# SoC_pwr_1.net
KiCad netlist of a schematic drawn in Altium Designer
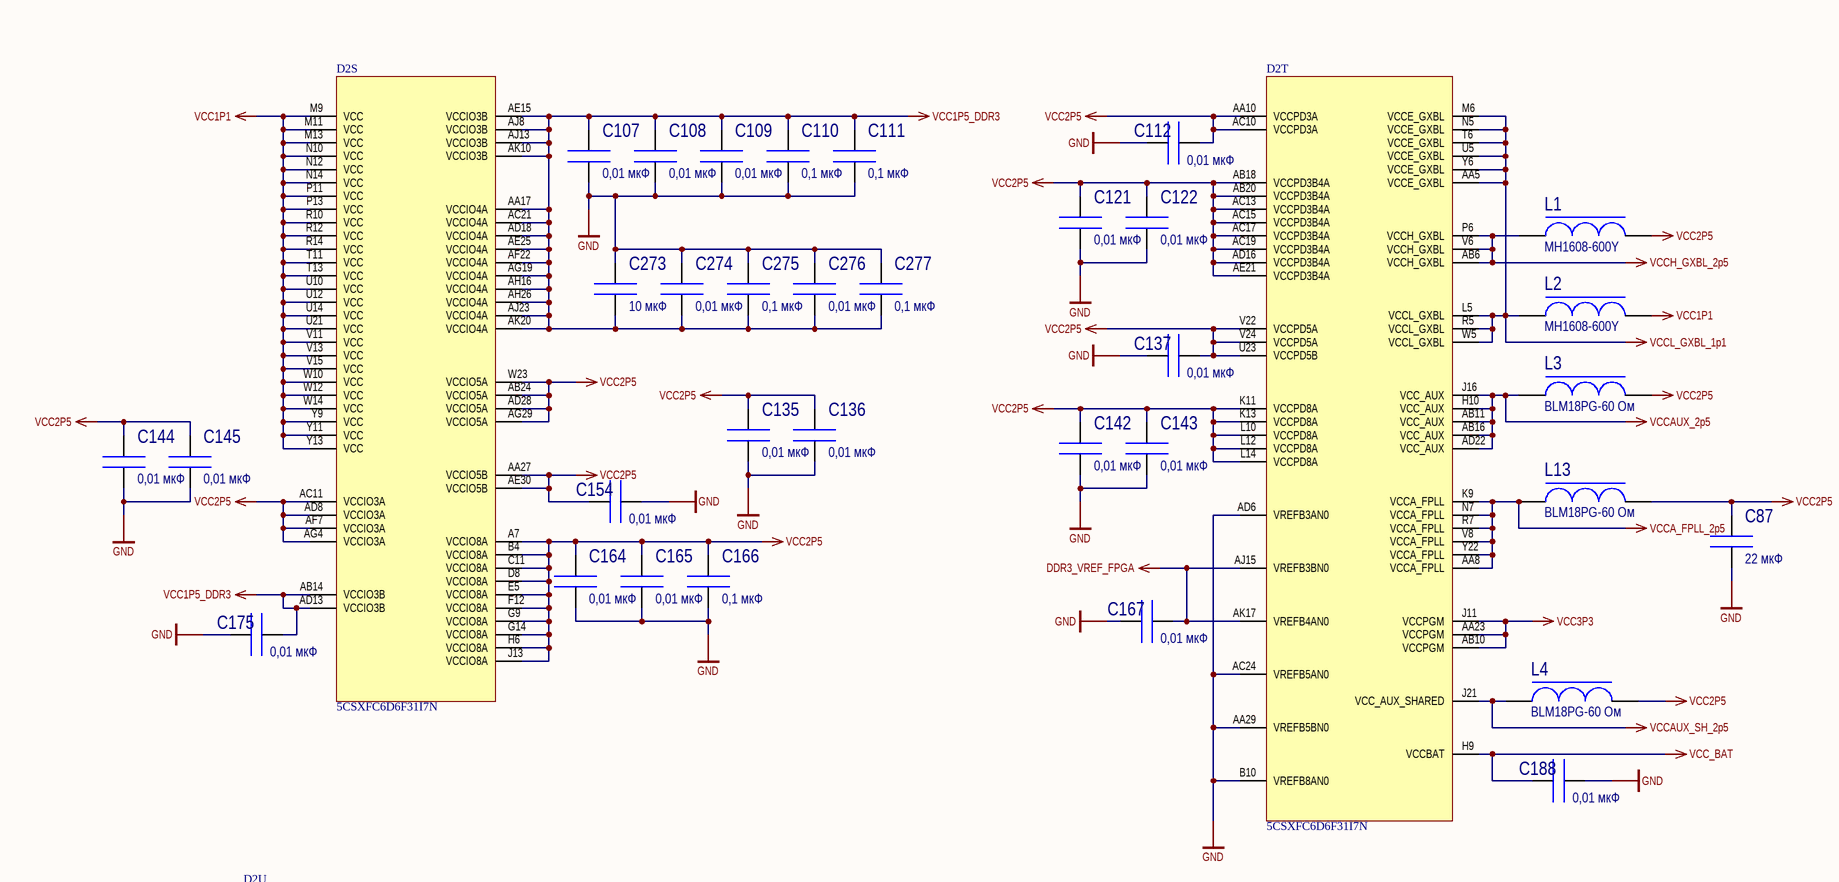
[diagram p0: SoC_pwr_1.SchDoc, top left]
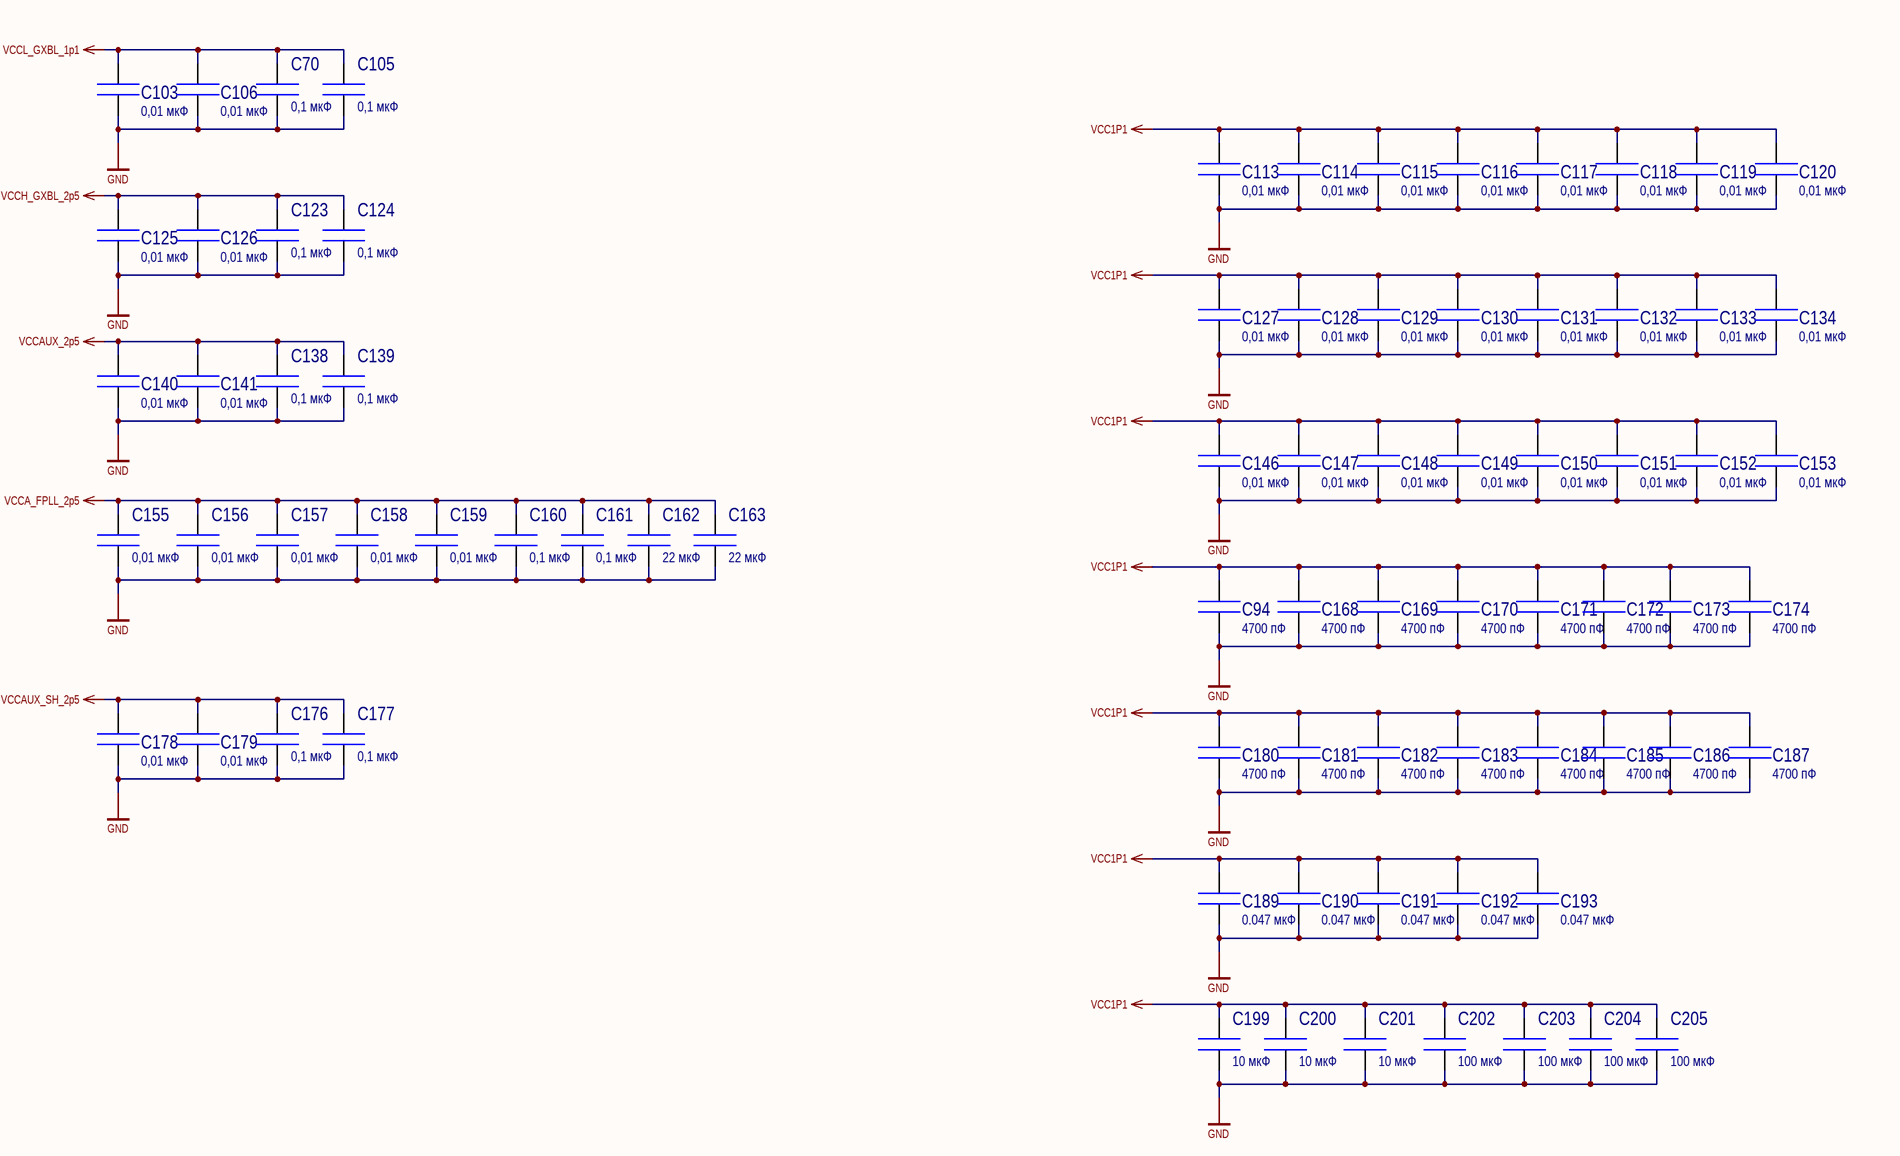
[diagram p1: SoC_pwr_1.SchDoc, top right]
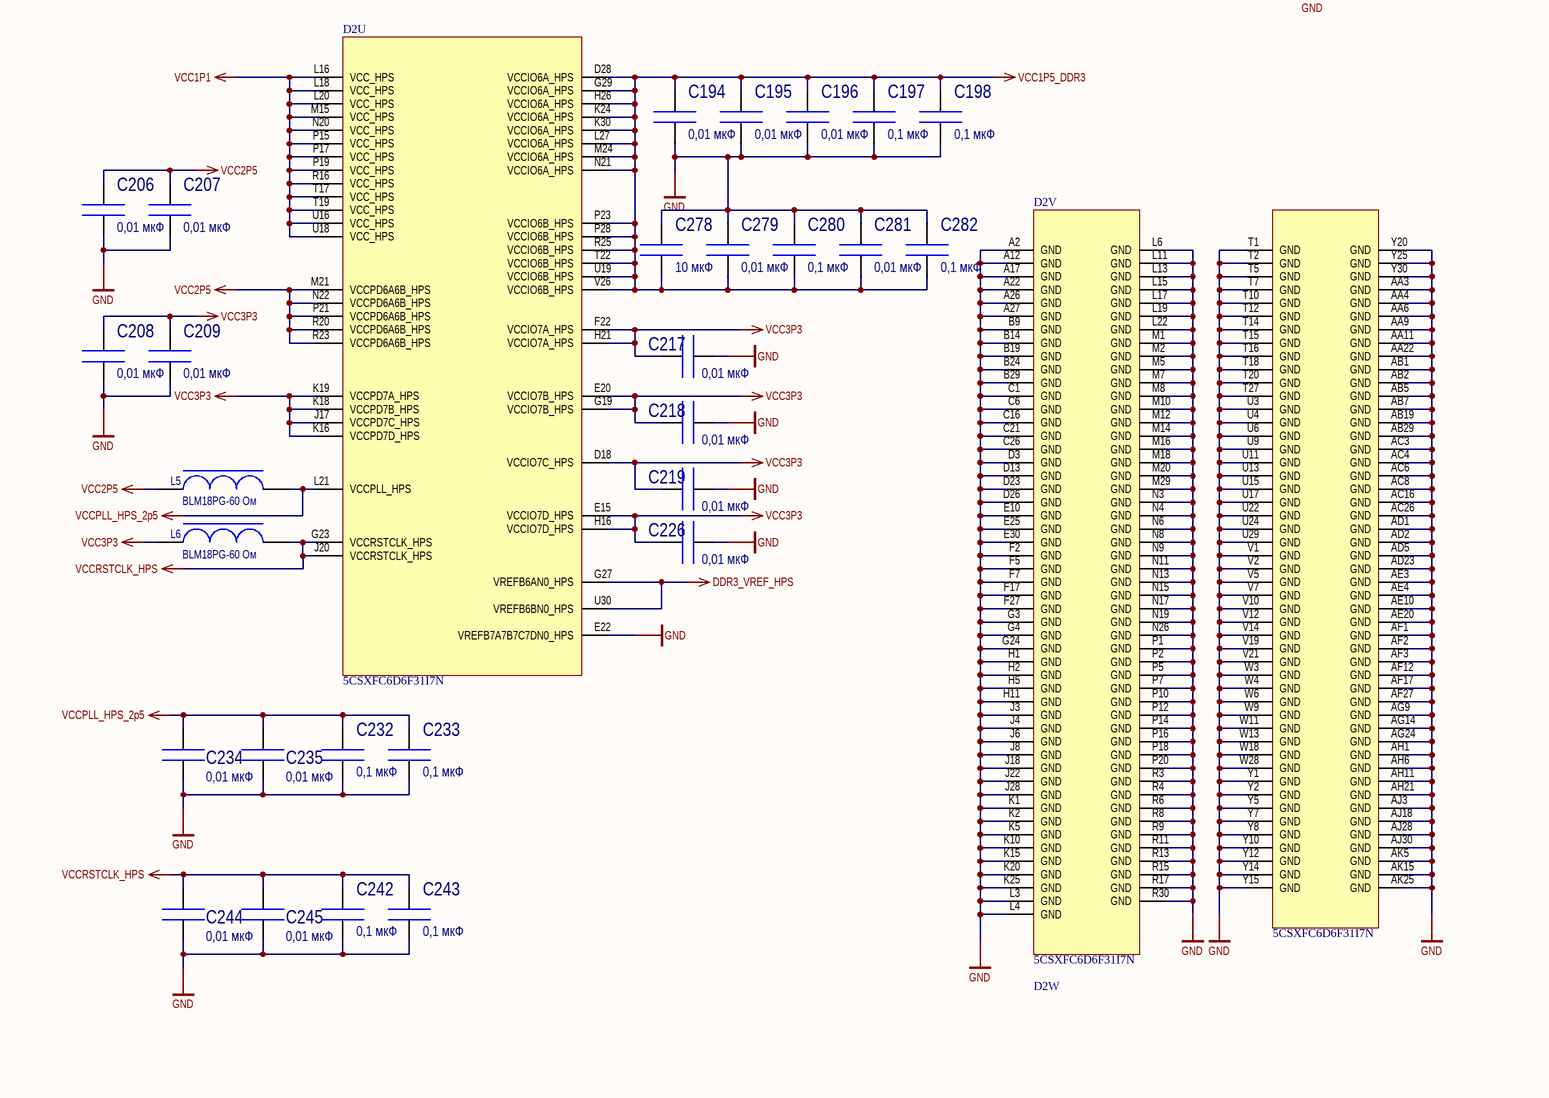
[diagram p2: SoC_pwr_1.SchDoc, bottom left]
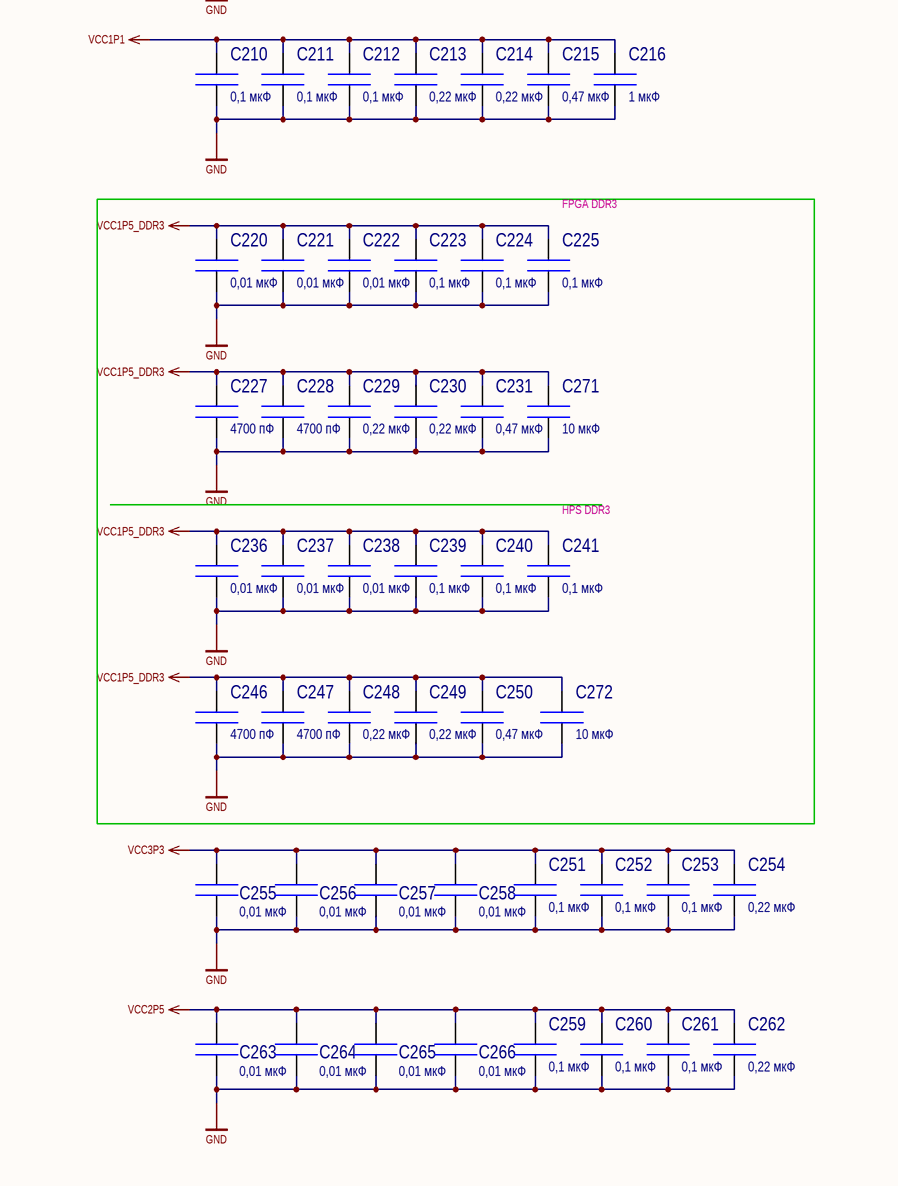
[diagram p3: SoC_pwr_1.SchDoc, bottom right]

(export (version "E")
  (design (tool "Eeschema 10.0.6"))
  (components
    (comp (ref "C70")
      (value "0,1 мкФ")
      (footprint "CC0402(1005)_OCT")
      (description "Чип конденсатор керамический")
      (fields (field (name "Comment") "CC0402-X7R-0,1 мкФ-20%-10В"))
      (libsource (lib "Чип конденсаторы") (part "CC0402-X7R-#-20%-10В"))
    )
    (comp (ref "C87")
      (value "22 мкФ")
      (footprint "CC0603")
      (description "Чип конденсатор керамический")
      (fields (field (name "Comment") "CC0603-X5R-22 мкФ-20%-6,3В"))
      (libsource (lib "Конденсаторы") (part "CC0603-X5R-#-20%-6,3В"))
    )
    (comp (ref "C94")
      (value "4700 пФ")
      (footprint "CC0402(1005)_OCT")
      (description "Чип конденсатор керамический")
      (fields (field (name "Comment") "CC0402-X7R-4700 пФ-10%-50В"))
      (libsource (lib "Чип конденсаторы") (part "CC0402-X7R-#-20%-10В"))
    )
    (comp (ref "C103")
      (value "0,01 мкФ")
      (footprint "CC0402(1005)_OCT")
      (description "Чип конденсатор керамический")
      (fields (field (name "Comment") "CC0402-X7R-0,01 мкФ-10%-50В"))
      (libsource (lib "Чип конденсаторы") (part "CC0402-X7R-#-20%-10В"))
    )
    (comp (ref "C105")
      (value "0,1 мкФ")
      (footprint "CC0402(1005)_OCT")
      (description "Чип конденсатор керамический")
      (fields (field (name "Comment") "CC0402-X7R-0,1 мкФ-20%-10В"))
      (libsource (lib "Чип конденсаторы") (part "CC0402-X7R-#-20%-10В"))
    )
    (comp (ref "C106")
      (value "0,01 мкФ")
      (footprint "CC0402(1005)_OCT")
      (description "Чип конденсатор керамический")
      (fields (field (name "Comment") "CC0402-X7R-0,01 мкФ-10%-50В"))
      (libsource (lib "Чип конденсаторы") (part "CC0402-X7R-#-20%-10В"))
    )
    (comp (ref "C107")
      (value "0,01 мкФ")
      (footprint "CC0402(1005)_OCT")
      (description "Чип конденсатор керамический")
      (fields (field (name "Comment") "CC0402-X7R-0,01 мкФ-10%-50В"))
      (libsource (lib "Чип конденсаторы") (part "CC0402-X7R-#-20%-10В"))
    )
    (comp (ref "C108")
      (value "0,01 мкФ")
      (footprint "CC0402(1005)_OCT")
      (description "Чип конденсатор керамический")
      (fields (field (name "Comment") "CC0402-X7R-0,01 мкФ-10%-50В"))
      (libsource (lib "Чип конденсаторы") (part "CC0402-X7R-#-20%-10В"))
    )
    (comp (ref "C109")
      (value "0,01 мкФ")
      (footprint "CC0402(1005)_OCT")
      (description "Чип конденсатор керамический")
      (fields (field (name "Comment") "CC0402-X7R-0,01 мкФ-10%-50В"))
      (libsource (lib "Чип конденсаторы") (part "CC0402-X7R-#-20%-10В"))
    )
    (comp (ref "C110")
      (value "0,1 мкФ")
      (footprint "CC0402(1005)_OCT")
      (description "Чип конденсатор керамический")
      (fields (field (name "Comment") "CC0402-X7R-0,1 мкФ-20%-10В"))
      (libsource (lib "Чип конденсаторы") (part "CC0402-X7R-#-20%-10В"))
    )
    (comp (ref "C111")
      (value "0,1 мкФ")
      (footprint "CC0402(1005)_OCT")
      (description "Чип конденсатор керамический")
      (fields (field (name "Comment") "CC0402-X7R-0,1 мкФ-20%-10В"))
      (libsource (lib "Чип конденсаторы") (part "CC0402-X7R-#-20%-10В"))
    )
    (comp (ref "C112")
      (value "0,01 мкФ")
      (footprint "CC0402(1005)_OCT")
      (description "Чип конденсатор керамический")
      (fields (field (name "Comment") "CC0402-X7R-0,01 мкФ-10%-50В"))
      (libsource (lib "Чип конденсаторы") (part "CC0402-X7R-#-20%-10В"))
    )
    (comp (ref "C113")
      (value "0,01 мкФ")
      (footprint "CC0402(1005)_OCT")
      (description "Чип конденсатор керамический")
      (fields (field (name "Comment") "CC0402-X7R-0,01 мкФ-10%-50В"))
      (libsource (lib "Чип конденсаторы") (part "CC0402-X7R-#-20%-10В"))
    )
    (comp (ref "C114")
      (value "0,01 мкФ")
      (footprint "CC0402(1005)_OCT")
      (description "Чип конденсатор керамический")
      (fields (field (name "Comment") "CC0402-X7R-0,01 мкФ-10%-50В"))
      (libsource (lib "Чип конденсаторы") (part "CC0402-X7R-#-20%-10В"))
    )
    (comp (ref "C115")
      (value "0,01 мкФ")
      (footprint "CC0402(1005)_OCT")
      (description "Чип конденсатор керамический")
      (fields (field (name "Comment") "CC0402-X7R-0,01 мкФ-10%-50В"))
      (libsource (lib "Чип конденсаторы") (part "CC0402-X7R-#-20%-10В"))
    )
    (comp (ref "C116")
      (value "0,01 мкФ")
      (footprint "CC0402(1005)_OCT")
      (description "Чип конденсатор керамический")
      (fields (field (name "Comment") "CC0402-X7R-0,01 мкФ-10%-50В"))
      (libsource (lib "Чип конденсаторы") (part "CC0402-X7R-#-20%-10В"))
    )
    (comp (ref "C117")
      (value "0,01 мкФ")
      (footprint "CC0402(1005)_OCT")
      (description "Чип конденсатор керамический")
      (fields (field (name "Comment") "CC0402-X7R-0,01 мкФ-10%-50В"))
      (libsource (lib "Чип конденсаторы") (part "CC0402-X7R-#-20%-10В"))
    )
    (comp (ref "C118")
      (value "0,01 мкФ")
      (footprint "CC0402(1005)_OCT")
      (description "Чип конденсатор керамический")
      (fields (field (name "Comment") "CC0402-X7R-0,01 мкФ-10%-50В"))
      (libsource (lib "Чип конденсаторы") (part "CC0402-X7R-#-20%-10В"))
    )
    (comp (ref "C119")
      (value "0,01 мкФ")
      (footprint "CC0402(1005)_OCT")
      (description "Чип конденсатор керамический")
      (fields (field (name "Comment") "CC0402-X7R-0,01 мкФ-10%-50В"))
      (libsource (lib "Чип конденсаторы") (part "CC0402-X7R-#-20%-10В"))
    )
    (comp (ref "C120")
      (value "0,01 мкФ")
      (footprint "CC0402(1005)_OCT")
      (description "Чип конденсатор керамический")
      (fields (field (name "Comment") "CC0402-X7R-0,01 мкФ-10%-50В"))
      (libsource (lib "Чип конденсаторы") (part "CC0402-X7R-#-20%-10В"))
    )
    (comp (ref "C121")
      (value "0,01 мкФ")
      (footprint "CC0402(1005)_OCT")
      (description "Чип конденсатор керамический")
      (fields (field (name "Comment") "CC0402-X7R-0,01 мкФ-10%-50В"))
      (libsource (lib "Чип конденсаторы") (part "CC0402-X7R-#-20%-10В"))
    )
    (comp (ref "C122")
      (value "0,01 мкФ")
      (footprint "CC0402(1005)_OCT")
      (description "Чип конденсатор керамический")
      (fields (field (name "Comment") "CC0402-X7R-0,01 мкФ-10%-50В"))
      (libsource (lib "Чип конденсаторы") (part "CC0402-X7R-#-20%-10В"))
    )
    (comp (ref "C123")
      (value "0,1 мкФ")
      (footprint "CC0402(1005)_OCT")
      (description "Чип конденсатор керамический")
      (fields (field (name "Comment") "CC0402-X7R-0,1 мкФ-20%-10В"))
      (libsource (lib "Чип конденсаторы") (part "CC0402-X7R-#-20%-10В"))
    )
    (comp (ref "C124")
      (value "0,1 мкФ")
      (footprint "CC0402(1005)_OCT")
      (description "Чип конденсатор керамический")
      (fields (field (name "Comment") "CC0402-X7R-0,1 мкФ-20%-10В"))
      (libsource (lib "Чип конденсаторы") (part "CC0402-X7R-#-20%-10В"))
    )
    (comp (ref "C125")
      (value "0,01 мкФ")
      (footprint "CC0402(1005)_OCT")
      (description "Чип конденсатор керамический")
      (fields (field (name "Comment") "CC0402-X7R-0,01 мкФ-10%-50В"))
      (libsource (lib "Чип конденсаторы") (part "CC0402-X7R-#-20%-10В"))
    )
    (comp (ref "C126")
      (value "0,01 мкФ")
      (footprint "CC0402(1005)_OCT")
      (description "Чип конденсатор керамический")
      (fields (field (name "Comment") "CC0402-X7R-0,01 мкФ-10%-50В"))
      (libsource (lib "Чип конденсаторы") (part "CC0402-X7R-#-20%-10В"))
    )
    (comp (ref "C127")
      (value "0,01 мкФ")
      (footprint "CC0402(1005)_OCT")
      (description "Чип конденсатор керамический")
      (fields (field (name "Comment") "CC0402-X7R-0,01 мкФ-10%-50В"))
      (libsource (lib "Чип конденсаторы") (part "CC0402-X7R-#-20%-10В"))
    )
    (comp (ref "C128")
      (value "0,01 мкФ")
      (footprint "CC0402(1005)_OCT")
      (description "Чип конденсатор керамический")
      (fields (field (name "Comment") "CC0402-X7R-0,01 мкФ-10%-50В"))
      (libsource (lib "Чип конденсаторы") (part "CC0402-X7R-#-20%-10В"))
    )
    (comp (ref "C129")
      (value "0,01 мкФ")
      (footprint "CC0402(1005)_OCT")
      (description "Чип конденсатор керамический")
      (fields (field (name "Comment") "CC0402-X7R-0,01 мкФ-10%-50В"))
      (libsource (lib "Чип конденсаторы") (part "CC0402-X7R-#-20%-10В"))
    )
    (comp (ref "C130")
      (value "0,01 мкФ")
      (footprint "CC0402(1005)_OCT")
      (description "Чип конденсатор керамический")
      (fields (field (name "Comment") "CC0402-X7R-0,01 мкФ-10%-50В"))
      (libsource (lib "Чип конденсаторы") (part "CC0402-X7R-#-20%-10В"))
    )
    (comp (ref "C131")
      (value "0,01 мкФ")
      (footprint "CC0402(1005)_OCT")
      (description "Чип конденсатор керамический")
      (fields (field (name "Comment") "CC0402-X7R-0,01 мкФ-10%-50В"))
      (libsource (lib "Чип конденсаторы") (part "CC0402-X7R-#-20%-10В"))
    )
    (comp (ref "C132")
      (value "0,01 мкФ")
      (footprint "CC0402(1005)_OCT")
      (description "Чип конденсатор керамический")
      (fields (field (name "Comment") "CC0402-X7R-0,01 мкФ-10%-50В"))
      (libsource (lib "Чип конденсаторы") (part "CC0402-X7R-#-20%-10В"))
    )
    (comp (ref "C133")
      (value "0,01 мкФ")
      (footprint "CC0402(1005)_OCT")
      (description "Чип конденсатор керамический")
      (fields (field (name "Comment") "CC0402-X7R-0,01 мкФ-10%-50В"))
      (libsource (lib "Чип конденсаторы") (part "CC0402-X7R-#-20%-10В"))
    )
    (comp (ref "C134")
      (value "0,01 мкФ")
      (footprint "CC0402(1005)_OCT")
      (description "Чип конденсатор керамический")
      (fields (field (name "Comment") "CC0402-X7R-0,01 мкФ-10%-50В"))
      (libsource (lib "Чип конденсаторы") (part "CC0402-X7R-#-20%-10В"))
    )
    (comp (ref "C135")
      (value "0,01 мкФ")
      (footprint "CC0402(1005)_OCT")
      (description "Чип конденсатор керамический")
      (fields (field (name "Comment") "CC0402-X7R-0,01 мкФ-10%-50В"))
      (libsource (lib "Чип конденсаторы") (part "CC0402-X7R-#-20%-10В"))
    )
    (comp (ref "C136")
      (value "0,01 мкФ")
      (footprint "CC0402(1005)_OCT")
      (description "Чип конденсатор керамический")
      (fields (field (name "Comment") "CC0402-X7R-0,01 мкФ-10%-50В"))
      (libsource (lib "Чип конденсаторы") (part "CC0402-X7R-#-20%-10В"))
    )
    (comp (ref "C137")
      (value "0,01 мкФ")
      (footprint "CC0402(1005)_OCT")
      (description "Чип конденсатор керамический")
      (fields (field (name "Comment") "CC0402-X7R-0,01 мкФ-10%-50В"))
      (libsource (lib "Чип конденсаторы") (part "CC0402-X7R-#-20%-10В"))
    )
    (comp (ref "C138")
      (value "0,1 мкФ")
      (footprint "CC0402(1005)_OCT")
      (description "Чип конденсатор керамический")
      (fields (field (name "Comment") "CC0402-X7R-0,1 мкФ-20%-10В"))
      (libsource (lib "Чип конденсаторы") (part "CC0402-X7R-#-20%-10В"))
    )
    (comp (ref "C139")
      (value "0,1 мкФ")
      (footprint "CC0402(1005)_OCT")
      (description "Чип конденсатор керамический")
      (fields (field (name "Comment") "CC0402-X7R-0,1 мкФ-20%-10В"))
      (libsource (lib "Чип конденсаторы") (part "CC0402-X7R-#-20%-10В"))
    )
    (comp (ref "C140")
      (value "0,01 мкФ")
      (footprint "CC0402(1005)_OCT")
      (description "Чип конденсатор керамический")
      (fields (field (name "Comment") "CC0402-X7R-0,01 мкФ-10%-50В"))
      (libsource (lib "Чип конденсаторы") (part "CC0402-X7R-#-20%-10В"))
    )
    (comp (ref "C141")
      (value "0,01 мкФ")
      (footprint "CC0402(1005)_OCT")
      (description "Чип конденсатор керамический")
      (fields (field (name "Comment") "CC0402-X7R-0,01 мкФ-10%-50В"))
      (libsource (lib "Чип конденсаторы") (part "CC0402-X7R-#-20%-10В"))
    )
    (comp (ref "C142")
      (value "0,01 мкФ")
      (footprint "CC0402(1005)_OCT")
      (description "Чип конденсатор керамический")
      (fields (field (name "Comment") "CC0402-X7R-0,01 мкФ-10%-50В"))
      (libsource (lib "Чип конденсаторы") (part "CC0402-X7R-#-20%-10В"))
    )
    (comp (ref "C143")
      (value "0,01 мкФ")
      (footprint "CC0402(1005)_OCT")
      (description "Чип конденсатор керамический")
      (fields (field (name "Comment") "CC0402-X7R-0,01 мкФ-10%-50В"))
      (libsource (lib "Чип конденсаторы") (part "CC0402-X7R-#-20%-10В"))
    )
    (comp (ref "C144")
      (value "0,01 мкФ")
      (footprint "CC0402(1005)_OCT")
      (description "Чип конденсатор керамический")
      (fields (field (name "Comment") "CC0402-X7R-0,01 мкФ-10%-50В"))
      (libsource (lib "Чип конденсаторы") (part "CC0402-X7R-#-20%-10В"))
    )
    (comp (ref "C145")
      (value "0,01 мкФ")
      (footprint "CC0402(1005)_OCT")
      (description "Чип конденсатор керамический")
      (fields (field (name "Comment") "CC0402-X7R-0,01 мкФ-10%-50В"))
      (libsource (lib "Чип конденсаторы") (part "CC0402-X7R-#-20%-10В"))
    )
    (comp (ref "C146")
      (value "0,01 мкФ")
      (footprint "CC0402(1005)_OCT")
      (description "Чип конденсатор керамический")
      (fields (field (name "Comment") "CC0402-X7R-0,01 мкФ-10%-50В"))
      (libsource (lib "Чип конденсаторы") (part "CC0402-X7R-#-20%-10В"))
    )
    (comp (ref "C147")
      (value "0,01 мкФ")
      (footprint "CC0402(1005)_OCT")
      (description "Чип конденсатор керамический")
      (fields (field (name "Comment") "CC0402-X7R-0,01 мкФ-10%-50В"))
      (libsource (lib "Чип конденсаторы") (part "CC0402-X7R-#-20%-10В"))
    )
    (comp (ref "C148")
      (value "0,01 мкФ")
      (footprint "CC0402(1005)_OCT")
      (description "Чип конденсатор керамический")
      (fields (field (name "Comment") "CC0402-X7R-0,01 мкФ-10%-50В"))
      (libsource (lib "Чип конденсаторы") (part "CC0402-X7R-#-20%-10В"))
    )
    (comp (ref "C149")
      (value "0,01 мкФ")
      (footprint "CC0402(1005)_OCT")
      (description "Чип конденсатор керамический")
      (fields (field (name "Comment") "CC0402-X7R-0,01 мкФ-10%-50В"))
      (libsource (lib "Чип конденсаторы") (part "CC0402-X7R-#-20%-10В"))
    )
    (comp (ref "C150")
      (value "0,01 мкФ")
      (footprint "CC0402(1005)_OCT")
      (description "Чип конденсатор керамический")
      (fields (field (name "Comment") "CC0402-X7R-0,01 мкФ-10%-50В"))
      (libsource (lib "Чип конденсаторы") (part "CC0402-X7R-#-20%-10В"))
    )
    (comp (ref "C151")
      (value "0,01 мкФ")
      (footprint "CC0402(1005)_OCT")
      (description "Чип конденсатор керамический")
      (fields (field (name "Comment") "CC0402-X7R-0,01 мкФ-10%-50В"))
      (libsource (lib "Чип конденсаторы") (part "CC0402-X7R-#-20%-10В"))
    )
    (comp (ref "C152")
      (value "0,01 мкФ")
      (footprint "CC0402(1005)_OCT")
      (description "Чип конденсатор керамический")
      (fields (field (name "Comment") "CC0402-X7R-0,01 мкФ-10%-50В"))
      (libsource (lib "Чип конденсаторы") (part "CC0402-X7R-#-20%-10В"))
    )
    (comp (ref "C153")
      (value "0,01 мкФ")
      (footprint "CC0402(1005)_OCT")
      (description "Чип конденсатор керамический")
      (fields (field (name "Comment") "CC0402-X7R-0,01 мкФ-10%-50В"))
      (libsource (lib "Чип конденсаторы") (part "CC0402-X7R-#-20%-10В"))
    )
    (comp (ref "C154")
      (value "0,01 мкФ")
      (footprint "CC0402(1005)_OCT")
      (description "Чип конденсатор керамический")
      (fields (field (name "Comment") "CC0402-X7R-0,01 мкФ-10%-50В"))
      (libsource (lib "Чип конденсаторы") (part "CC0402-X7R-#-20%-10В"))
    )
    (comp (ref "C155")
      (value "0,01 мкФ")
      (footprint "CC0402(1005)_OCT")
      (description "Чип конденсатор керамический")
      (fields (field (name "Comment") "CC0402-X7R-0,01 мкФ-10%-50В"))
      (libsource (lib "Чип конденсаторы") (part "CC0402-X7R-#-20%-10В"))
    )
    (comp (ref "C156")
      (value "0,01 мкФ")
      (footprint "CC0402(1005)_OCT")
      (description "Чип конденсатор керамический")
      (fields (field (name "Comment") "CC0402-X7R-0,01 мкФ-10%-50В"))
      (libsource (lib "Чип конденсаторы") (part "CC0402-X7R-#-20%-10В"))
    )
    (comp (ref "C157")
      (value "0,01 мкФ")
      (footprint "CC0402(1005)_OCT")
      (description "Чип конденсатор керамический")
      (fields (field (name "Comment") "CC0402-X7R-0,01 мкФ-10%-50В"))
      (libsource (lib "Чип конденсаторы") (part "CC0402-X7R-#-20%-10В"))
    )
    (comp (ref "C158")
      (value "0,01 мкФ")
      (footprint "CC0402(1005)_OCT")
      (description "Чип конденсатор керамический")
      (fields (field (name "Comment") "CC0402-X7R-0,01 мкФ-10%-50В"))
      (libsource (lib "Чип конденсаторы") (part "CC0402-X7R-#-20%-10В"))
    )
    (comp (ref "C159")
      (value "0,01 мкФ")
      (footprint "CC0402(1005)_OCT")
      (description "Чип конденсатор керамический")
      (fields (field (name "Comment") "CC0402-X7R-0,01 мкФ-10%-50В"))
      (libsource (lib "Чип конденсаторы") (part "CC0402-X7R-#-20%-10В"))
    )
    (comp (ref "C160")
      (value "0,1 мкФ")
      (footprint "CC0402(1005)_OCT")
      (description "Чип конденсатор керамический")
      (fields (field (name "Comment") "CC0402-X7R-0,1 мкФ-20%-10В"))
      (libsource (lib "Чип конденсаторы") (part "CC0402-X7R-#-20%-10В"))
    )
    (comp (ref "C161")
      (value "0,1 мкФ")
      (footprint "CC0402(1005)_OCT")
      (description "Чип конденсатор керамический")
      (fields (field (name "Comment") "CC0402-X7R-0,1 мкФ-20%-10В"))
      (libsource (lib "Чип конденсаторы") (part "CC0402-X7R-#-20%-10В"))
    )
    (comp (ref "C162")
      (value "22 мкФ")
      (footprint "CC0603")
      (description "Чип конденсатор керамический")
      (fields (field (name "Comment") "CC0603-X5R-22 мкФ-20%-6,3В"))
      (libsource (lib "Конденсаторы") (part "CC0603-X5R-#-20%-6,3В"))
    )
    (comp (ref "C163")
      (value "22 мкФ")
      (footprint "CC0603")
      (description "Чип конденсатор керамический")
      (fields (field (name "Comment") "CC0603-X5R-22 мкФ-20%-6,3В"))
      (libsource (lib "Конденсаторы") (part "CC0603-X5R-#-20%-6,3В"))
    )
    (comp (ref "C164")
      (value "0,01 мкФ")
      (footprint "CC0402(1005)_OCT")
      (description "Чип конденсатор керамический")
      (fields (field (name "Comment") "CC0402-X7R-0,01 мкФ-10%-50В"))
      (libsource (lib "Чип конденсаторы") (part "CC0402-X7R-#-20%-10В"))
    )
    (comp (ref "C165")
      (value "0,01 мкФ")
      (footprint "CC0402(1005)_OCT")
      (description "Чип конденсатор керамический")
      (fields (field (name "Comment") "CC0402-X7R-0,01 мкФ-10%-50В"))
      (libsource (lib "Чип конденсаторы") (part "CC0402-X7R-#-20%-10В"))
    )
    (comp (ref "C166")
      (value "0,1 мкФ")
      (footprint "CC0402(1005)_OCT")
      (description "Чип конденсатор керамический")
      (fields (field (name "Comment") "CC0402-X7R-0,1 мкФ-20%-10В"))
      (libsource (lib "Чип конденсаторы") (part "CC0402-X7R-#-20%-10В"))
    )
    (comp (ref "C167")
      (value "0,01 мкФ")
      (footprint "CC0402(1005)_OCT")
      (description "Чип конденсатор керамический")
      (fields (field (name "Comment") "CC0402-X7R-0,01 мкФ-10%-50В"))
      (libsource (lib "Чип конденсаторы") (part "CC0402-X7R-#-20%-10В"))
    )
    (comp (ref "C168")
      (value "4700 пФ")
      (footprint "CC0402(1005)_OCT")
      (description "Чип конденсатор керамический")
      (fields (field (name "Comment") "CC0402-X7R-4700 пФ-10%-50В"))
      (libsource (lib "Чип конденсаторы") (part "CC0402-X7R-#-20%-10В"))
    )
    (comp (ref "C169")
      (value "4700 пФ")
      (footprint "CC0402(1005)_OCT")
      (description "Чип конденсатор керамический")
      (fields (field (name "Comment") "CC0402-X7R-4700 пФ-10%-50В"))
      (libsource (lib "Чип конденсаторы") (part "CC0402-X7R-#-20%-10В"))
    )
    (comp (ref "C170")
      (value "4700 пФ")
      (footprint "CC0402(1005)_OCT")
      (description "Чип конденсатор керамический")
      (fields (field (name "Comment") "CC0402-X7R-4700 пФ-10%-50В"))
      (libsource (lib "Чип конденсаторы") (part "CC0402-X7R-#-20%-10В"))
    )
    (comp (ref "C171")
      (value "4700 пФ")
      (footprint "CC0402(1005)_OCT")
      (description "Чип конденсатор керамический")
      (fields (field (name "Comment") "CC0402-X7R-4700 пФ-10%-50В"))
      (libsource (lib "Чип конденсаторы") (part "CC0402-X7R-#-20%-10В"))
    )
    (comp (ref "C172")
      (value "4700 пФ")
      (footprint "CC0402(1005)_OCT")
      (description "Чип конденсатор керамический")
      (fields (field (name "Comment") "CC0402-X7R-4700 пФ-10%-50В"))
      (libsource (lib "Чип конденсаторы") (part "CC0402-X7R-#-20%-10В"))
    )
    (comp (ref "C173")
      (value "4700 пФ")
      (footprint "CC0402(1005)_OCT")
      (description "Чип конденсатор керамический")
      (fields (field (name "Comment") "CC0402-X7R-4700 пФ-10%-50В"))
      (libsource (lib "Чип конденсаторы") (part "CC0402-X7R-#-20%-10В"))
    )
    (comp (ref "C174")
      (value "4700 пФ")
      (footprint "CC0402(1005)_OCT")
      (description "Чип конденсатор керамический")
      (fields (field (name "Comment") "CC0402-X7R-4700 пФ-10%-50В"))
      (libsource (lib "Чип конденсаторы") (part "CC0402-X7R-#-20%-10В"))
    )
    (comp (ref "C175")
      (value "0,01 мкФ")
      (footprint "CC0402(1005)_OCT")
      (description "Чип конденсатор керамический")
      (fields (field (name "Comment") "CC0402-X7R-0,01 мкФ-10%-50В"))
      (libsource (lib "Чип конденсаторы") (part "CC0402-X7R-#-20%-10В"))
    )
    (comp (ref "C176")
      (value "0,1 мкФ")
      (footprint "CC0402(1005)_OCT")
      (description "Чип конденсатор керамический")
      (fields (field (name "Comment") "CC0402-X7R-0,1 мкФ-20%-10В"))
      (libsource (lib "Чип конденсаторы") (part "CC0402-X7R-#-20%-10В"))
    )
    (comp (ref "C177")
      (value "0,1 мкФ")
      (footprint "CC0402(1005)")
      (description "Чип конденсатор керамический")
      (fields (field (name "Comment") "CC0402-X7R-0,1 мкФ-20%-10В"))
      (libsource (lib "Чип конденсаторы") (part "CC0402-X7R-#-20%-10В"))
    )
    (comp (ref "C178")
      (value "0,01 мкФ")
      (footprint "CC0402(1005)_OCT")
      (description "Чип конденсатор керамический")
      (fields (field (name "Comment") "CC0402-X7R-0,01 мкФ-10%-50В"))
      (libsource (lib "Чип конденсаторы") (part "CC0402-X7R-#-20%-10В"))
    )
    (comp (ref "C179")
      (value "0,01 мкФ")
      (footprint "CC0402(1005)")
      (description "Чип конденсатор керамический")
      (fields (field (name "Comment") "CC0402-X7R-0,01 мкФ-10%-50В"))
      (libsource (lib "Чип конденсаторы") (part "CC0402-X7R-#-20%-10В"))
    )
    (comp (ref "C180")
      (value "4700 пФ")
      (footprint "CC0402(1005)_OCT")
      (description "Чип конденсатор керамический")
      (fields (field (name "Comment") "CC0402-X7R-4700 пФ-10%-50В"))
      (libsource (lib "Чип конденсаторы") (part "CC0402-X7R-#-20%-10В"))
    )
    (comp (ref "C181")
      (value "4700 пФ")
      (footprint "CC0402(1005)_OCT")
      (description "Чип конденсатор керамический")
      (fields (field (name "Comment") "CC0402-X7R-4700 пФ-10%-50В"))
      (libsource (lib "Чип конденсаторы") (part "CC0402-X7R-#-20%-10В"))
    )
    (comp (ref "C182")
      (value "4700 пФ")
      (footprint "CC0402(1005)_OCT")
      (description "Чип конденсатор керамический")
      (fields (field (name "Comment") "CC0402-X7R-4700 пФ-10%-50В"))
      (libsource (lib "Чип конденсаторы") (part "CC0402-X7R-#-20%-10В"))
    )
    (comp (ref "C183")
      (value "4700 пФ")
      (footprint "CC0402(1005)_OCT")
      (description "Чип конденсатор керамический")
      (fields (field (name "Comment") "CC0402-X7R-4700 пФ-10%-50В"))
      (libsource (lib "Чип конденсаторы") (part "CC0402-X7R-#-20%-10В"))
    )
    (comp (ref "C184")
      (value "4700 пФ")
      (footprint "CC0402(1005)_OCT")
      (description "Чип конденсатор керамический")
      (fields (field (name "Comment") "CC0402-X7R-4700 пФ-10%-50В"))
      (libsource (lib "Чип конденсаторы") (part "CC0402-X7R-#-20%-10В"))
    )
    (comp (ref "C185")
      (value "4700 пФ")
      (footprint "CC0402(1005)_OCT")
      (description "Чип конденсатор керамический")
      (fields (field (name "Comment") "CC0402-X7R-4700 пФ-10%-50В"))
      (libsource (lib "Чип конденсаторы") (part "CC0402-X7R-#-20%-10В"))
    )
    (comp (ref "C186")
      (value "4700 пФ")
      (footprint "CC0402(1005)_OCT")
      (description "Чип конденсатор керамический")
      (fields (field (name "Comment") "CC0402-X7R-4700 пФ-10%-50В"))
      (libsource (lib "Чип конденсаторы") (part "CC0402-X7R-#-20%-10В"))
    )
    (comp (ref "C187")
      (value "4700 пФ")
      (footprint "CC0402(1005)_OCT")
      (description "Чип конденсатор керамический")
      (fields (field (name "Comment") "CC0402-X7R-4700 пФ-10%-50В"))
      (libsource (lib "Чип конденсаторы") (part "CC0402-X7R-#-20%-10В"))
    )
    (comp (ref "C188")
      (value "0,01 мкФ")
      (footprint "CC0402(1005)_OCT")
      (description "Чип конденсатор керамический")
      (fields (field (name "Comment") "CC0402-X7R-0,01 мкФ-10%-50В"))
      (libsource (lib "Чип конденсаторы") (part "CC0402-X7R-#-20%-10В"))
    )
    (comp (ref "C189")
      (value "0.047 мкФ")
      (footprint "CC0402(1005)_OCT")
      (description "Чип конденсатор керамический")
      (fields (field (name "Comment") "CC0402-X7R-0.047 мкФ-10%-50В"))
      (libsource (lib "Чип конденсаторы") (part "CC0402-X7R-#-20%-10В"))
    )
    (comp (ref "C190")
      (value "0.047 мкФ")
      (footprint "CC0402(1005)_OCT")
      (description "Чип конденсатор керамический")
      (fields (field (name "Comment") "CC0402-X7R-0.047 мкФ-10%-50В"))
      (libsource (lib "Чип конденсаторы") (part "CC0402-X7R-#-20%-10В"))
    )
    (comp (ref "C191")
      (value "0.047 мкФ")
      (footprint "CC0402(1005)_OCT")
      (description "Чип конденсатор керамический")
      (fields (field (name "Comment") "CC0402-X7R-0.047 мкФ-10%-50В"))
      (libsource (lib "Чип конденсаторы") (part "CC0402-X7R-#-20%-10В"))
    )
    (comp (ref "C192")
      (value "0.047 мкФ")
      (footprint "CC0402(1005)_OCT")
      (description "Чип конденсатор керамический")
      (fields (field (name "Comment") "CC0402-X7R-0.047 мкФ-10%-50В"))
      (libsource (lib "Чип конденсаторы") (part "CC0402-X7R-#-20%-10В"))
    )
    (comp (ref "C193")
      (value "0.047 мкФ")
      (footprint "CC0402(1005)_OCT")
      (description "Чип конденсатор керамический")
      (fields (field (name "Comment") "CC0402-X7R-0.047 мкФ-10%-50В"))
      (libsource (lib "Чип конденсаторы") (part "CC0402-X7R-#-20%-10В"))
    )
    (comp (ref "C194")
      (value "0,01 мкФ")
      (footprint "CC0402(1005)_OCT")
      (description "Чип конденсатор керамический")
      (fields (field (name "Comment") "CC0402-X7R-0,01 мкФ-10%-50В"))
      (libsource (lib "Чип конденсаторы") (part "CC0402-X7R-#-20%-10В"))
    )
    (comp (ref "C195")
      (value "0,01 мкФ")
      (footprint "CC0402(1005)_OCT")
      (description "Чип конденсатор керамический")
      (fields (field (name "Comment") "CC0402-X7R-0,01 мкФ-10%-50В"))
      (libsource (lib "Чип конденсаторы") (part "CC0402-X7R-#-20%-10В"))
    )
    (comp (ref "C196")
      (value "0,01 мкФ")
      (footprint "CC0402(1005)_OCT")
      (description "Чип конденсатор керамический")
      (fields (field (name "Comment") "CC0402-X7R-0,01 мкФ-10%-50В"))
      (libsource (lib "Чип конденсаторы") (part "CC0402-X7R-#-20%-10В"))
    )
    (comp (ref "C197")
      (value "0,1 мкФ")
      (footprint "CC0402(1005)_OCT")
      (description "Чип конденсатор керамический")
      (fields (field (name "Comment") "CC0402-X7R-0,1 мкФ-20%-10В"))
      (libsource (lib "Чип конденсаторы") (part "CC0402-X7R-#-20%-10В"))
    )
    (comp (ref "C198")
      (value "0,1 мкФ")
      (footprint "CC0402(1005)_OCT")
      (description "Чип конденсатор керамический")
      (fields (field (name "Comment") "CC0402-X7R-0,1 мкФ-20%-10В"))
      (libsource (lib "Чип конденсаторы") (part "CC0402-X7R-#-20%-10В"))
    )
    (comp (ref "C199")
      (value "10 мкФ")
      (footprint "CC0402(1005)_OCT")
      (description "Чип конденсатор керамический")
      (fields (field (name "Comment") "CC0402-X5R-10 мкФ-20%-6.3В"))
      (libsource (lib "Чип конденсаторы") (part "CC0402-X7R-#-20%-10В"))
    )
    (comp (ref "C200")
      (value "10 мкФ")
      (footprint "CC0402(1005)_OCT")
      (description "Чип конденсатор керамический")
      (fields (field (name "Comment") "CC0402-X5R-10 мкФ-20%-6.3В"))
      (libsource (lib "Чип конденсаторы") (part "CC0402-X7R-#-20%-10В"))
    )
    (comp (ref "C201")
      (value "10 мкФ")
      (footprint "CC0402(1005)_OCT")
      (description "Чип конденсатор керамический")
      (fields (field (name "Comment") "CC0402-X5R-10 мкФ-20%-6.3В"))
      (libsource (lib "Чип конденсаторы") (part "CC0402-X7R-#-20%-10В"))
    )
    (comp (ref "C202")
      (value "100 мкФ")
      (footprint "CC0805")
      (description "Чип конденсатор керамический")
      (fields (field (name "Comment") "CC0805-X5R-100 мкФ-20%-4В"))
      (libsource (lib "Конденсаторы") (part "CC0805-X7R-#-20%-25В"))
    )
    (comp (ref "C203")
      (value "100 мкФ")
      (footprint "CC0805")
      (description "Чип конденсатор керамический")
      (fields (field (name "Comment") "CC0805-X5R-100 мкФ-20%-4В"))
      (libsource (lib "Конденсаторы") (part "CC0805-X7R-#-20%-25В"))
    )
    (comp (ref "C204")
      (value "100 мкФ")
      (footprint "CC0805")
      (description "Чип конденсатор керамический")
      (fields (field (name "Comment") "CC0805-X5R-100 мкФ-20%-4В"))
      (libsource (lib "Конденсаторы") (part "CC0805-X7R-#-20%-25В"))
    )
    (comp (ref "C205")
      (value "100 мкФ")
      (footprint "CC0805")
      (description "Чип конденсатор керамический")
      (fields (field (name "Comment") "CC0805-X5R-100 мкФ-20%-4В"))
      (libsource (lib "Конденсаторы") (part "CC0805-X7R-#-20%-25В"))
    )
    (comp (ref "C206")
      (value "0,01 мкФ")
      (footprint "CC0402(1005)_OCT")
      (description "Чип конденсатор керамический")
      (fields (field (name "Comment") "CC0402-X7R-0,01 мкФ-10%-50В"))
      (libsource (lib "Чип конденсаторы") (part "CC0402-X7R-#-20%-10В"))
    )
    (comp (ref "C207")
      (value "0,01 мкФ")
      (footprint "CC0402(1005)_OCT")
      (description "Чип конденсатор керамический")
      (fields (field (name "Comment") "CC0402-X7R-0,01 мкФ-10%-50В"))
      (libsource (lib "Чип конденсаторы") (part "CC0402-X7R-#-20%-10В"))
    )
    (comp (ref "C208")
      (value "0,01 мкФ")
      (footprint "CC0402(1005)_OCT")
      (description "Чип конденсатор керамический")
      (fields (field (name "Comment") "CC0402-X7R-0,01 мкФ-10%-50В"))
      (libsource (lib "Чип конденсаторы") (part "CC0402-X7R-#-20%-10В"))
    )
    (comp (ref "C209")
      (value "0,01 мкФ")
      (footprint "CC0402(1005)_OCT")
      (description "Чип конденсатор керамический")
      (fields (field (name "Comment") "CC0402-X7R-0,01 мкФ-10%-50В"))
      (libsource (lib "Чип конденсаторы") (part "CC0402-X7R-#-20%-10В"))
    )
    (comp (ref "C210")
      (value "0,1 мкФ")
      (footprint "CC0402(1005)_OCT")
      (description "Чип конденсатор керамический")
      (fields (field (name "Comment") "CC0402-X7R-0,1 мкФ-20%-10В"))
      (libsource (lib "Чип конденсаторы") (part "CC0402-X7R-#-20%-10В"))
    )
    (comp (ref "C211")
      (value "0,1 мкФ")
      (footprint "CC0402(1005)_OCT")
      (description "Чип конденсатор керамический")
      (fields (field (name "Comment") "CC0402-X7R-0,1 мкФ-20%-10В"))
      (libsource (lib "Чип конденсаторы") (part "CC0402-X7R-#-20%-10В"))
    )
    (comp (ref "C212")
      (value "0,1 мкФ")
      (footprint "CC0402(1005)_OCT")
      (description "Чип конденсатор керамический")
      (fields (field (name "Comment") "CC0402-X7R-0,1 мкФ-20%-10В"))
      (libsource (lib "Чип конденсаторы") (part "CC0402-X7R-#-20%-10В"))
    )
    (comp (ref "C213")
      (value "0,22 мкФ")
      (footprint "CC0402(1005)_OCT")
      (description "Чип конденсатор керамический")
      (fields (field (name "Comment") "CC0402-X7R-0,22 мкФ-10%-6.3В"))
      (libsource (lib "Чип конденсаторы") (part "CC0402-X7R-#-20%-10В"))
    )
    (comp (ref "C214")
      (value "0,22 мкФ")
      (footprint "CC0402(1005)_OCT")
      (description "Чип конденсатор керамический")
      (fields (field (name "Comment") "CC0402-X7R-0,22 мкФ-10%-6.3В"))
      (libsource (lib "Чип конденсаторы") (part "CC0402-X7R-#-20%-10В"))
    )
    (comp (ref "C215")
      (value "0,47 мкФ")
      (footprint "CC0402(1005)_OCT")
      (description "Чип конденсатор керамический")
      (fields (field (name "Comment") "CC0402-X7R-0,47 мкФ-10%-6.3В"))
      (libsource (lib "Чип конденсаторы") (part "CC0402-X7R-#-20%-10В"))
    )
    (comp (ref "C216")
      (value "1 мкФ")
      (footprint "CC0402(1005)_OCT")
      (description "Чип конденсатор керамический")
      (fields (field (name "Comment") "CC0402-X5R-1 мкФ-10%-6.3В"))
      (libsource (lib "Чип конденсаторы") (part "CC0402-X7R-#-20%-10В"))
    )
    (comp (ref "C217")
      (value "0,01 мкФ")
      (footprint "CC0402(1005)_OCT")
      (description "Чип конденсатор керамический")
      (fields (field (name "Comment") "CC0402-X7R-0,01 мкФ-10%-50В"))
      (libsource (lib "Чип конденсаторы") (part "CC0402-X7R-#-20%-10В"))
    )
    (comp (ref "C218")
      (value "0,01 мкФ")
      (footprint "CC0402(1005)_OCT")
      (description "Чип конденсатор керамический")
      (fields (field (name "Comment") "CC0402-X7R-0,01 мкФ-10%-50В"))
      (libsource (lib "Чип конденсаторы") (part "CC0402-X7R-#-20%-10В"))
    )
    (comp (ref "C219")
      (value "0,01 мкФ")
      (footprint "CC0402(1005)_OCT")
      (description "Чип конденсатор керамический")
      (fields (field (name "Comment") "CC0402-X7R-0,01 мкФ-10%-50В"))
      (libsource (lib "Чип конденсаторы") (part "CC0402-X7R-#-20%-10В"))
    )
    (comp (ref "C220")
      (value "0,01 мкФ")
      (footprint "CC0402(1005)")
      (description "Чип конденсатор керамический")
      (fields (field (name "Comment") "CC0402-X7R-0,01 мкФ-10%-50В"))
      (libsource (lib "Чип конденсаторы") (part "CC0402-X7R-#-20%-10В"))
    )
    (comp (ref "C221")
      (value "0,01 мкФ")
      (footprint "CC0402(1005)")
      (description "Чип конденсатор керамический")
      (fields (field (name "Comment") "CC0402-X7R-0,01 мкФ-10%-50В"))
      (libsource (lib "Чип конденсаторы") (part "CC0402-X7R-#-20%-10В"))
    )
    (comp (ref "C222")
      (value "0,01 мкФ")
      (footprint "CC0402(1005)")
      (description "Чип конденсатор керамический")
      (fields (field (name "Comment") "CC0402-X7R-0,01 мкФ-10%-50В"))
      (libsource (lib "Чип конденсаторы") (part "CC0402-X7R-#-20%-10В"))
    )
    (comp (ref "C223")
      (value "0,1 мкФ")
      (footprint "CC0402(1005)")
      (description "Чип конденсатор керамический")
      (fields (field (name "Comment") "CC0402-X7R-0,1 мкФ-20%-10В"))
      (libsource (lib "Чип конденсаторы") (part "CC0402-X7R-#-20%-10В"))
    )
    (comp (ref "C224")
      (value "0,1 мкФ")
      (footprint "CC0402(1005)")
      (description "Чип конденсатор керамический")
      (fields (field (name "Comment") "CC0402-X7R-0,1 мкФ-20%-10В"))
      (libsource (lib "Чип конденсаторы") (part "CC0402-X7R-#-20%-10В"))
    )
    (comp (ref "C225")
      (value "0,1 мкФ")
      (footprint "CC0402(1005)")
      (description "Чип конденсатор керамический")
      (fields (field (name "Comment") "CC0402-X7R-0,1 мкФ-20%-10В"))
      (libsource (lib "Чип конденсаторы") (part "CC0402-X7R-#-20%-10В"))
    )
    (comp (ref "C226")
      (value "0,01 мкФ")
      (footprint "CC0402(1005)_OCT")
      (description "Чип конденсатор керамический")
      (fields (field (name "Comment") "CC0402-X7R-0,01 мкФ-10%-50В"))
      (libsource (lib "Чип конденсаторы") (part "CC0402-X7R-#-20%-10В"))
    )
    (comp (ref "C227")
      (value "4700 пФ")
      (footprint "CC0402(1005)")
      (description "Чип конденсатор керамический")
      (fields (field (name "Comment") "CC0402-X7R-4700 пФ-10%-50В"))
      (libsource (lib "Чип конденсаторы") (part "CC0402-X7R-#-20%-10В"))
    )
    (comp (ref "C228")
      (value "4700 пФ")
      (footprint "CC0402(1005)")
      (description "Чип конденсатор керамический")
      (fields (field (name "Comment") "CC0402-X7R-4700 пФ-10%-50В"))
      (libsource (lib "Чип конденсаторы") (part "CC0402-X7R-#-20%-10В"))
    )
    (comp (ref "C229")
      (value "0,22 мкФ")
      (footprint "CC0402(1005)")
      (description "Чип конденсатор керамический")
      (fields (field (name "Comment") "CC0402-X7R-0,22 мкФ-10%-6.3В"))
      (libsource (lib "Чип конденсаторы") (part "CC0402-X7R-#-20%-10В"))
    )
    (comp (ref "C230")
      (value "0,22 мкФ")
      (footprint "CC0402(1005)")
      (description "Чип конденсатор керамический")
      (fields (field (name "Comment") "CC0402-X7R-0,22 мкФ-10%-6.3В"))
      (libsource (lib "Чип конденсаторы") (part "CC0402-X7R-#-20%-10В"))
    )
    (comp (ref "C231")
      (value "0,47 мкФ")
      (footprint "CC0402(1005)")
      (description "Чип конденсатор керамический")
      (fields (field (name "Comment") "CC0402-X7R-0,47 мкФ-10%-6.3В"))
      (libsource (lib "Чип конденсаторы") (part "CC0402-X7R-#-20%-10В"))
    )
    (comp (ref "C232")
      (value "0,1 мкФ")
      (footprint "CC0402(1005)_OCT")
      (description "Чип конденсатор керамический")
      (fields (field (name "Comment") "CC0402-X7R-0,1 мкФ-20%-10В"))
      (libsource (lib "Чип конденсаторы") (part "CC0402-X7R-#-20%-10В"))
    )
    (comp (ref "C233")
      (value "0,1 мкФ")
      (footprint "CC0402(1005)_OCT")
      (description "Чип конденсатор керамический")
      (fields (field (name "Comment") "CC0402-X7R-0,1 мкФ-20%-10В"))
      (libsource (lib "Чип конденсаторы") (part "CC0402-X7R-#-20%-10В"))
    )
    (comp (ref "C234")
      (value "0,01 мкФ")
      (footprint "CC0402(1005)_OCT")
      (description "Чип конденсатор керамический")
      (fields (field (name "Comment") "CC0402-X7R-0,01 мкФ-10%-50В"))
      (libsource (lib "Чип конденсаторы") (part "CC0402-X7R-#-20%-10В"))
    )
    (comp (ref "C235")
      (value "0,01 мкФ")
      (footprint "CC0402(1005)_OCT")
      (description "Чип конденсатор керамический")
      (fields (field (name "Comment") "CC0402-X7R-0,01 мкФ-10%-50В"))
      (libsource (lib "Чип конденсаторы") (part "CC0402-X7R-#-20%-10В"))
    )
    (comp (ref "C236")
      (value "0,01 мкФ")
      (footprint "CC0402(1005)")
      (description "Чип конденсатор керамический")
      (fields (field (name "Comment") "CC0402-X7R-0,01 мкФ-10%-50В"))
      (libsource (lib "Чип конденсаторы") (part "CC0402-X7R-#-20%-10В"))
    )
    (comp (ref "C237")
      (value "0,01 мкФ")
      (footprint "CC0402(1005)")
      (description "Чип конденсатор керамический")
      (fields (field (name "Comment") "CC0402-X7R-0,01 мкФ-10%-50В"))
      (libsource (lib "Чип конденсаторы") (part "CC0402-X7R-#-20%-10В"))
    )
    (comp (ref "C238")
      (value "0,01 мкФ")
      (footprint "CC0402(1005)")
      (description "Чип конденсатор керамический")
      (fields (field (name "Comment") "CC0402-X7R-0,01 мкФ-10%-50В"))
      (libsource (lib "Чип конденсаторы") (part "CC0402-X7R-#-20%-10В"))
    )
    (comp (ref "C239")
      (value "0,1 мкФ")
      (footprint "CC0402(1005)")
      (description "Чип конденсатор керамический")
      (fields (field (name "Comment") "CC0402-X7R-0,1 мкФ-20%-10В"))
      (libsource (lib "Чип конденсаторы") (part "CC0402-X7R-#-20%-10В"))
    )
    (comp (ref "C240")
      (value "0,1 мкФ")
      (footprint "CC0402(1005)")
      (description "Чип конденсатор керамический")
      (fields (field (name "Comment") "CC0402-X7R-0,1 мкФ-20%-10В"))
      (libsource (lib "Чип конденсаторы") (part "CC0402-X7R-#-20%-10В"))
    )
    (comp (ref "C241")
      (value "0,1 мкФ")
      (footprint "CC0402(1005)")
      (description "Чип конденсатор керамический")
      (fields (field (name "Comment") "CC0402-X7R-0,1 мкФ-20%-10В"))
      (libsource (lib "Чип конденсаторы") (part "CC0402-X7R-#-20%-10В"))
    )
    (comp (ref "C242")
      (value "0,1 мкФ")
      (footprint "CC0402(1005)_OCT")
      (description "Чип конденсатор керамический")
      (fields (field (name "Comment") "CC0402-X7R-0,1 мкФ-20%-10В"))
      (libsource (lib "Чип конденсаторы") (part "CC0402-X7R-#-20%-10В"))
    )
    (comp (ref "C243")
      (value "0,1 мкФ")
      (footprint "CC0402(1005)_OCT")
      (description "Чип конденсатор керамический")
      (fields (field (name "Comment") "CC0402-X7R-0,1 мкФ-20%-10В"))
      (libsource (lib "Чип конденсаторы") (part "CC0402-X7R-#-20%-10В"))
    )
    (comp (ref "C244")
      (value "0,01 мкФ")
      (footprint "CC0402(1005)_OCT")
      (description "Чип конденсатор керамический")
      (fields (field (name "Comment") "CC0402-X7R-0,01 мкФ-10%-50В"))
      (libsource (lib "Чип конденсаторы") (part "CC0402-X7R-#-20%-10В"))
    )
    (comp (ref "C245")
      (value "0,01 мкФ")
      (footprint "CC0402(1005)_OCT")
      (description "Чип конденсатор керамический")
      (fields (field (name "Comment") "CC0402-X7R-0,01 мкФ-10%-50В"))
      (libsource (lib "Чип конденсаторы") (part "CC0402-X7R-#-20%-10В"))
    )
    (comp (ref "C246")
      (value "4700 пФ")
      (footprint "CC0402(1005)")
      (description "Чип конденсатор керамический")
      (fields (field (name "Comment") "CC0402-X7R-4700 пФ-10%-50В"))
      (libsource (lib "Чип конденсаторы") (part "CC0402-X7R-#-20%-10В"))
    )
    (comp (ref "C247")
      (value "4700 пФ")
      (footprint "CC0402(1005)")
      (description "Чип конденсатор керамический")
      (fields (field (name "Comment") "CC0402-X7R-4700 пФ-10%-50В"))
      (libsource (lib "Чип конденсаторы") (part "CC0402-X7R-#-20%-10В"))
    )
    (comp (ref "C248")
      (value "0,22 мкФ")
      (footprint "CC0402(1005)")
      (description "Чип конденсатор керамический")
      (fields (field (name "Comment") "CC0402-X7R-0,22 мкФ-10%-6.3В"))
      (libsource (lib "Чип конденсаторы") (part "CC0402-X7R-#-20%-10В"))
    )
    (comp (ref "C249")
      (value "0,22 мкФ")
      (footprint "CC0402(1005)")
      (description "Чип конденсатор керамический")
      (fields (field (name "Comment") "CC0402-X7R-0,22 мкФ-10%-6.3В"))
      (libsource (lib "Чип конденсаторы") (part "CC0402-X7R-#-20%-10В"))
    )
    (comp (ref "C250")
      (value "0,47 мкФ")
      (footprint "CC0402(1005)")
      (description "Чип конденсатор керамический")
      (fields (field (name "Comment") "CC0402-X7R-0,47 мкФ-10%-6.3В"))
      (libsource (lib "Чип конденсаторы") (part "CC0402-X7R-#-20%-10В"))
    )
    (comp (ref "C251")
      (value "0,1 мкФ")
      (footprint "CC0402(1005)_OCT")
      (description "Чип конденсатор керамический")
      (fields (field (name "Comment") "CC0402-X7R-0,1 мкФ-20%-10В"))
      (libsource (lib "Чип конденсаторы") (part "CC0402-X7R-#-20%-10В"))
    )
    (comp (ref "C252")
      (value "0,1 мкФ")
      (footprint "CC0402(1005)_OCT")
      (description "Чип конденсатор керамический")
      (fields (field (name "Comment") "CC0402-X7R-0,1 мкФ-20%-10В"))
      (libsource (lib "Чип конденсаторы") (part "CC0402-X7R-#-20%-10В"))
    )
    (comp (ref "C253")
      (value "0,1 мкФ")
      (footprint "CC0402(1005)_OCT")
      (description "Чип конденсатор керамический")
      (fields (field (name "Comment") "CC0402-X7R-0,1 мкФ-20%-10В"))
      (libsource (lib "Чип конденсаторы") (part "CC0402-X7R-#-20%-10В"))
    )
    (comp (ref "C254")
      (value "0,22 мкФ")
      (footprint "CC0402(1005)_OCT")
      (description "Чип конденсатор керамический")
      (fields (field (name "Comment") "CC0402-X7R-0,22 мкФ-10%-6.3В"))
      (libsource (lib "Чип конденсаторы") (part "CC0402-X7R-#-20%-10В"))
    )
    (comp (ref "C255")
      (value "0,01 мкФ")
      (footprint "CC0402(1005)_OCT")
      (description "Чип конденсатор керамический")
      (fields (field (name "Comment") "CC0402-X7R-0,01 мкФ-10%-50В"))
      (libsource (lib "Чип конденсаторы") (part "CC0402-X7R-#-20%-10В"))
    )
    (comp (ref "C256")
      (value "0,01 мкФ")
      (footprint "CC0402(1005)_OCT")
      (description "Чип конденсатор керамический")
      (fields (field (name "Comment") "CC0402-X7R-0,01 мкФ-10%-50В"))
      (libsource (lib "Чип конденсаторы") (part "CC0402-X7R-#-20%-10В"))
    )
    (comp (ref "C257")
      (value "0,01 мкФ")
      (footprint "CC0402(1005)_OCT")
      (description "Чип конденсатор керамический")
      (fields (field (name "Comment") "CC0402-X7R-0,01 мкФ-10%-50В"))
      (libsource (lib "Чип конденсаторы") (part "CC0402-X7R-#-20%-10В"))
    )
    (comp (ref "C258")
      (value "0,01 мкФ")
      (footprint "CC0402(1005)_OCT")
      (description "Чип конденсатор керамический")
      (fields (field (name "Comment") "CC0402-X7R-0,01 мкФ-10%-50В"))
      (libsource (lib "Чип конденсаторы") (part "CC0402-X7R-#-20%-10В"))
    )
    (comp (ref "C259")
      (value "0,1 мкФ")
      (footprint "CC0402(1005)_OCT")
      (description "Чип конденсатор керамический")
      (fields (field (name "Comment") "CC0402-X7R-0,1 мкФ-20%-10В"))
      (libsource (lib "Чип конденсаторы") (part "CC0402-X7R-#-20%-10В"))
    )
    (comp (ref "C260")
      (value "0,1 мкФ")
      (footprint "CC0402(1005)_OCT")
      (description "Чип конденсатор керамический")
      (fields (field (name "Comment") "CC0402-X7R-0,1 мкФ-20%-10В"))
      (libsource (lib "Чип конденсаторы") (part "CC0402-X7R-#-20%-10В"))
    )
    (comp (ref "C261")
      (value "0,1 мкФ")
      (footprint "CC0402(1005)_OCT")
      (description "Чип конденсатор керамический")
      (fields (field (name "Comment") "CC0402-X7R-0,1 мкФ-20%-10В"))
      (libsource (lib "Чип конденсаторы") (part "CC0402-X7R-#-20%-10В"))
    )
    (comp (ref "C262")
      (value "0,22 мкФ")
      (footprint "CC0402(1005)_OCT")
      (description "Чип конденсатор керамический")
      (fields (field (name "Comment") "CC0402-X7R-0,22 мкФ-10%-6.3В"))
      (libsource (lib "Чип конденсаторы") (part "CC0402-X7R-#-20%-10В"))
    )
    (comp (ref "C263")
      (value "0,01 мкФ")
      (footprint "CC0402(1005)_OCT")
      (description "Чип конденсатор керамический")
      (fields (field (name "Comment") "CC0402-X7R-0,01 мкФ-10%-50В"))
      (libsource (lib "Чип конденсаторы") (part "CC0402-X7R-#-20%-10В"))
    )
    (comp (ref "C264")
      (value "0,01 мкФ")
      (footprint "CC0402(1005)_OCT")
      (description "Чип конденсатор керамический")
      (fields (field (name "Comment") "CC0402-X7R-0,01 мкФ-10%-50В"))
      (libsource (lib "Чип конденсаторы") (part "CC0402-X7R-#-20%-10В"))
    )
    (comp (ref "C265")
      (value "0,01 мкФ")
      (footprint "CC0402(1005)_OCT")
      (description "Чип конденсатор керамический")
      (fields (field (name "Comment") "CC0402-X7R-0,01 мкФ-10%-50В"))
      (libsource (lib "Чип конденсаторы") (part "CC0402-X7R-#-20%-10В"))
    )
    (comp (ref "C266")
      (value "0,01 мкФ")
      (footprint "CC0402(1005)_OCT")
      (description "Чип конденсатор керамический")
      (fields (field (name "Comment") "CC0402-X7R-0,01 мкФ-10%-50В"))
      (libsource (lib "Чип конденсаторы") (part "CC0402-X7R-#-20%-10В"))
    )
    (comp (ref "C271")
      (value "10 мкФ")
      (footprint "CC0402(1005)")
      (description "Чип конденсатор керамический")
      (fields (field (name "Comment") "CC0402-X5R-10 мкФ-20%-6.3В"))
      (libsource (lib "Чип конденсаторы") (part "CC0402-X7R-#-20%-10В"))
    )
    (comp (ref "C272")
      (value "10 мкФ")
      (footprint "CC0402(1005)")
      (description "Чип конденсатор керамический")
      (fields (field (name "Comment") "CC0402-X5R-10 мкФ-20%-6.3В"))
      (libsource (lib "Чип конденсаторы") (part "CC0402-X7R-#-20%-10В"))
    )
    (comp (ref "C273")
      (value "10 мкФ")
      (footprint "CC0402(1005)")
      (description "Чип конденсатор керамический")
      (fields (field (name "Comment") "CC0402-X5R-10 мкФ-20%-6.3В"))
      (libsource (lib "Чип конденсаторы") (part "CC0402-X7R-#-20%-10В"))
    )
    (comp (ref "C274")
      (value "0,01 мкФ")
      (footprint "CC0402(1005)")
      (description "Чип конденсатор керамический")
      (fields (field (name "Comment") "CC0402-X7R-0,01 мкФ-10%-50В"))
      (libsource (lib "Чип конденсаторы") (part "CC0402-X7R-#-20%-10В"))
    )
    (comp (ref "C275")
      (value "0,1 мкФ")
      (footprint "CC0402(1005)")
      (description "Чип конденсатор керамический")
      (fields (field (name "Comment") "CC0402-X7R-0,1 мкФ-20%-10В"))
      (libsource (lib "Чип конденсаторы") (part "CC0402-X7R-#-20%-10В"))
    )
    (comp (ref "C276")
      (value "0,01 мкФ")
      (footprint "CC0402(1005)")
      (description "Чип конденсатор керамический")
      (fields (field (name "Comment") "CC0402-X7R-0,01 мкФ-10%-50В"))
      (libsource (lib "Чип конденсаторы") (part "CC0402-X7R-#-20%-10В"))
    )
    (comp (ref "C277")
      (value "0,1 мкФ")
      (footprint "CC0402(1005)")
      (description "Чип конденсатор керамический")
      (fields (field (name "Comment") "CC0402-X7R-0,1 мкФ-20%-10В"))
      (libsource (lib "Чип конденсаторы") (part "CC0402-X7R-#-20%-10В"))
    )
    (comp (ref "C278")
      (value "10 мкФ")
      (footprint "CC0402(1005)")
      (description "Чип конденсатор керамический")
      (fields (field (name "Comment") "CC0402-X5R-10 мкФ-20%-6.3В"))
      (libsource (lib "Чип конденсаторы") (part "CC0402-X7R-#-20%-10В"))
    )
    (comp (ref "C279")
      (value "0,01 мкФ")
      (footprint "CC0402(1005)")
      (description "Чип конденсатор керамический")
      (fields (field (name "Comment") "CC0402-X7R-0,01 мкФ-10%-50В"))
      (libsource (lib "Чип конденсаторы") (part "CC0402-X7R-#-20%-10В"))
    )
    (comp (ref "C280")
      (value "0,1 мкФ")
      (footprint "CC0402(1005)")
      (description "Чип конденсатор керамический")
      (fields (field (name "Comment") "CC0402-X7R-0,1 мкФ-20%-10В"))
      (libsource (lib "Чип конденсаторы") (part "CC0402-X7R-#-20%-10В"))
    )
    (comp (ref "C281")
      (value "0,01 мкФ")
      (footprint "CC0402(1005)")
      (description "Чип конденсатор керамический")
      (fields (field (name "Comment") "CC0402-X7R-0,01 мкФ-10%-50В"))
      (libsource (lib "Чип конденсаторы") (part "CC0402-X7R-#-20%-10В"))
    )
    (comp (ref "C282")
      (value "0,1 мкФ")
      (footprint "CC0402(1005)")
      (description "Чип конденсатор керамический")
      (fields (field (name "Comment") "CC0402-X7R-0,1 мкФ-20%-10В"))
      (libsource (lib "Чип конденсаторы") (part "CC0402-X7R-#-20%-10В"))
    )
    (comp (ref "D2")
      (value "5CSXFC6D6F31I7N")
      (footprint "ALTR-FBGA896_A-200")
      (fields (field (name "MANUFACTURER") "Altera"))
      (libsource (lib "Altera Cyclone V_sd") (part "5CSXFC6D6F31I7N"))
    )
    (comp (ref "L1")
      (value "MH1608-600Y")
      (footprint "CL0805")
      (description "Чип индуктивность подавления EMP")
      (libsource (lib "Индуктивности") (part "BLM21"))
    )
    (comp (ref "L2")
      (value "MH1608-600Y")
      (footprint "CL0805")
      (description "Чип индуктивность подавления EMP")
      (libsource (lib "Индуктивности") (part "BLM21"))
    )
    (comp (ref "L3")
      (value "BLM18PG-60 Ом")
      (footprint "CL0603")
      (description "Чип индуктивность подавления EMP")
      (libsource (lib "Индуктивности") (part "BLM18"))
    )
    (comp (ref "L4")
      (value "BLM18PG-60 Ом")
      (footprint "CL0603")
      (description "Чип индуктивность подавления EMP")
      (libsource (lib "Индуктивности") (part "BLM18"))
    )
    (comp (ref "L5")
      (value "BLM18PG-60 Ом")
      (footprint "CL0603")
      (description "Чип индуктивность подавления EMP")
      (libsource (lib "Индуктивности") (part "BLM18"))
    )
    (comp (ref "L6")
      (value "BLM18PG-60 Ом")
      (footprint "CL0603")
      (description "Чип индуктивность подавления EMP")
      (libsource (lib "Индуктивности") (part "BLM18"))
    )
    (comp (ref "L13")
      (value "BLM18PG-60 Ом")
      (footprint "CL0603")
      (description "Чип индуктивность подавления EMP")
      (libsource (lib "Индуктивности") (part "BLM18"))
    )
  )
  (nets
    (net (code "1") (name "DDR3_VREF_FPGA") (class "Default")
      (node (ref "C167") (pin "1") (pinfunction "+_1") (pintype "passive"))
      (node (ref "D2") (pin "AJ15") (pinfunction "VREFB3BN0_AJ15") (pintype "power_in"))
      (node (ref "D2") (pin "AK17") (pinfunction "VREFB4AN0_AK17") (pintype "power_in"))
    )
    (net (code "2") (name "DDR3_VREF_HPS") (class "Default")
      (node (ref "D2") (pin "G27") (pinfunction "VREFB6AN0_HPS_G27") (pintype "power_in"))
      (node (ref "D2") (pin "U30") (pinfunction "VREFB6BN0_HPS_U30") (pintype "power_in"))
    )
    (net (code "3") (name "GND") (class "Default")
      (node (ref "C103") (pin "1") (pinfunction "+_1") (pintype "passive"))
      (node (ref "C105") (pin "1") (pinfunction "+_1") (pintype "passive"))
      (node (ref "C106") (pin "1") (pinfunction "+_1") (pintype "passive"))
      (node (ref "C107") (pin "1") (pinfunction "+_1") (pintype "passive"))
      (node (ref "C108") (pin "1") (pinfunction "+_1") (pintype "passive"))
      (node (ref "C109") (pin "1") (pinfunction "+_1") (pintype "passive"))
      (node (ref "C110") (pin "1") (pinfunction "+_1") (pintype "passive"))
      (node (ref "C111") (pin "1") (pinfunction "+_1") (pintype "passive"))
      (node (ref "C112") (pin "2") (pinfunction "-_2") (pintype "passive"))
      (node (ref "C113") (pin "1") (pinfunction "+_1") (pintype "passive"))
      (node (ref "C114") (pin "1") (pinfunction "+_1") (pintype "passive"))
      (node (ref "C115") (pin "1") (pinfunction "+_1") (pintype "passive"))
      (node (ref "C116") (pin "1") (pinfunction "+_1") (pintype "passive"))
      (node (ref "C117") (pin "1") (pinfunction "+_1") (pintype "passive"))
      (node (ref "C118") (pin "1") (pinfunction "+_1") (pintype "passive"))
      (node (ref "C119") (pin "1") (pinfunction "+_1") (pintype "passive"))
      (node (ref "C120") (pin "1") (pinfunction "+_1") (pintype "passive"))
      (node (ref "C121") (pin "1") (pinfunction "+_1") (pintype "passive"))
      (node (ref "C122") (pin "1") (pinfunction "+_1") (pintype "passive"))
      (node (ref "C123") (pin "1") (pinfunction "+_1") (pintype "passive"))
      (node (ref "C124") (pin "1") (pinfunction "+_1") (pintype "passive"))
      (node (ref "C125") (pin "1") (pinfunction "+_1") (pintype "passive"))
      (node (ref "C126") (pin "1") (pinfunction "+_1") (pintype "passive"))
      (node (ref "C127") (pin "1") (pinfunction "+_1") (pintype "passive"))
      (node (ref "C128") (pin "1") (pinfunction "+_1") (pintype "passive"))
      (node (ref "C129") (pin "1") (pinfunction "+_1") (pintype "passive"))
      (node (ref "C130") (pin "1") (pinfunction "+_1") (pintype "passive"))
      (node (ref "C131") (pin "1") (pinfunction "+_1") (pintype "passive"))
      (node (ref "C132") (pin "1") (pinfunction "+_1") (pintype "passive"))
      (node (ref "C133") (pin "1") (pinfunction "+_1") (pintype "passive"))
      (node (ref "C134") (pin "1") (pinfunction "+_1") (pintype "passive"))
      (node (ref "C135") (pin "1") (pinfunction "+_1") (pintype "passive"))
      (node (ref "C136") (pin "1") (pinfunction "+_1") (pintype "passive"))
      (node (ref "C137") (pin "2") (pinfunction "-_2") (pintype "passive"))
      (node (ref "C138") (pin "1") (pinfunction "+_1") (pintype "passive"))
      (node (ref "C139") (pin "1") (pinfunction "+_1") (pintype "passive"))
      (node (ref "C140") (pin "1") (pinfunction "+_1") (pintype "passive"))
      (node (ref "C141") (pin "1") (pinfunction "+_1") (pintype "passive"))
      (node (ref "C142") (pin "1") (pinfunction "+_1") (pintype "passive"))
      (node (ref "C143") (pin "1") (pinfunction "+_1") (pintype "passive"))
      (node (ref "C144") (pin "1") (pinfunction "+_1") (pintype "passive"))
      (node (ref "C145") (pin "1") (pinfunction "+_1") (pintype "passive"))
      (node (ref "C146") (pin "1") (pinfunction "+_1") (pintype "passive"))
      (node (ref "C147") (pin "1") (pinfunction "+_1") (pintype "passive"))
      (node (ref "C148") (pin "1") (pinfunction "+_1") (pintype "passive"))
      (node (ref "C149") (pin "1") (pinfunction "+_1") (pintype "passive"))
      (node (ref "C150") (pin "1") (pinfunction "+_1") (pintype "passive"))
      (node (ref "C151") (pin "1") (pinfunction "+_1") (pintype "passive"))
      (node (ref "C152") (pin "1") (pinfunction "+_1") (pintype "passive"))
      (node (ref "C153") (pin "1") (pinfunction "+_1") (pintype "passive"))
      (node (ref "C154") (pin "2") (pinfunction "-_2") (pintype "passive"))
      (node (ref "C155") (pin "1") (pinfunction "+_1") (pintype "passive"))
      (node (ref "C156") (pin "1") (pinfunction "+_1") (pintype "passive"))
      (node (ref "C157") (pin "1") (pinfunction "+_1") (pintype "passive"))
      (node (ref "C158") (pin "1") (pinfunction "+_1") (pintype "passive"))
      (node (ref "C159") (pin "1") (pinfunction "+_1") (pintype "passive"))
      (node (ref "C160") (pin "1") (pinfunction "+_1") (pintype "passive"))
      (node (ref "C161") (pin "1") (pinfunction "+_1") (pintype "passive"))
      (node (ref "C162") (pin "2") (pinfunction "-_2") (pintype "passive"))
      (node (ref "C163") (pin "2") (pinfunction "-_2") (pintype "passive"))
      (node (ref "C164") (pin "1") (pinfunction "+_1") (pintype "passive"))
      (node (ref "C165") (pin "1") (pinfunction "+_1") (pintype "passive"))
      (node (ref "C166") (pin "1") (pinfunction "+_1") (pintype "passive"))
      (node (ref "C167") (pin "2") (pinfunction "-_2") (pintype "passive"))
      (node (ref "C168") (pin "2") (pinfunction "-_2") (pintype "passive"))
      (node (ref "C169") (pin "2") (pinfunction "-_2") (pintype "passive"))
      (node (ref "C170") (pin "2") (pinfunction "-_2") (pintype "passive"))
      (node (ref "C171") (pin "2") (pinfunction "-_2") (pintype "passive"))
      (node (ref "C172") (pin "2") (pinfunction "-_2") (pintype "passive"))
      (node (ref "C173") (pin "2") (pinfunction "-_2") (pintype "passive"))
      (node (ref "C174") (pin "2") (pinfunction "-_2") (pintype "passive"))
      (node (ref "C175") (pin "2") (pinfunction "-_2") (pintype "passive"))
      (node (ref "C176") (pin "1") (pinfunction "+_1") (pintype "passive"))
      (node (ref "C177") (pin "1") (pinfunction "+_1") (pintype "passive"))
      (node (ref "C178") (pin "1") (pinfunction "+_1") (pintype "passive"))
      (node (ref "C179") (pin "1") (pinfunction "+_1") (pintype "passive"))
      (node (ref "C180") (pin "2") (pinfunction "-_2") (pintype "passive"))
      (node (ref "C181") (pin "2") (pinfunction "-_2") (pintype "passive"))
      (node (ref "C182") (pin "2") (pinfunction "-_2") (pintype "passive"))
      (node (ref "C183") (pin "2") (pinfunction "-_2") (pintype "passive"))
      (node (ref "C184") (pin "2") (pinfunction "-_2") (pintype "passive"))
      (node (ref "C185") (pin "2") (pinfunction "-_2") (pintype "passive"))
      (node (ref "C186") (pin "2") (pinfunction "-_2") (pintype "passive"))
      (node (ref "C187") (pin "2") (pinfunction "-_2") (pintype "passive"))
      (node (ref "C188") (pin "2") (pinfunction "-_2") (pintype "passive"))
      (node (ref "C189") (pin "2") (pinfunction "-_2") (pintype "passive"))
      (node (ref "C190") (pin "2") (pinfunction "-_2") (pintype "passive"))
      (node (ref "C191") (pin "2") (pinfunction "-_2") (pintype "passive"))
      (node (ref "C192") (pin "2") (pinfunction "-_2") (pintype "passive"))
      (node (ref "C193") (pin "2") (pinfunction "-_2") (pintype "passive"))
      (node (ref "C194") (pin "1") (pinfunction "+_1") (pintype "passive"))
      (node (ref "C195") (pin "1") (pinfunction "+_1") (pintype "passive"))
      (node (ref "C196") (pin "1") (pinfunction "+_1") (pintype "passive"))
      (node (ref "C197") (pin "1") (pinfunction "+_1") (pintype "passive"))
      (node (ref "C198") (pin "1") (pinfunction "+_1") (pintype "passive"))
      (node (ref "C199") (pin "1") (pinfunction "+_1") (pintype "passive"))
      (node (ref "C200") (pin "1") (pinfunction "+_1") (pintype "passive"))
      (node (ref "C201") (pin "1") (pinfunction "+_1") (pintype "passive"))
      (node (ref "C202") (pin "2") (pinfunction "-_2") (pintype "passive"))
      (node (ref "C203") (pin "2") (pinfunction "-_2") (pintype "passive"))
      (node (ref "C204") (pin "2") (pinfunction "-_2") (pintype "passive"))
      (node (ref "C205") (pin "2") (pinfunction "-_2") (pintype "passive"))
      (node (ref "C206") (pin "1") (pinfunction "+_1") (pintype "passive"))
      (node (ref "C207") (pin "1") (pinfunction "+_1") (pintype "passive"))
      (node (ref "C208") (pin "1") (pinfunction "+_1") (pintype "passive"))
      (node (ref "C209") (pin "1") (pinfunction "+_1") (pintype "passive"))
      (node (ref "C210") (pin "1") (pinfunction "+_1") (pintype "passive"))
      (node (ref "C211") (pin "1") (pinfunction "+_1") (pintype "passive"))
      (node (ref "C212") (pin "1") (pinfunction "+_1") (pintype "passive"))
      (node (ref "C213") (pin "1") (pinfunction "+_1") (pintype "passive"))
      (node (ref "C214") (pin "1") (pinfunction "+_1") (pintype "passive"))
      (node (ref "C215") (pin "1") (pinfunction "+_1") (pintype "passive"))
      (node (ref "C216") (pin "1") (pinfunction "+_1") (pintype "passive"))
      (node (ref "C217") (pin "1") (pinfunction "+_1") (pintype "passive"))
      (node (ref "C218") (pin "1") (pinfunction "+_1") (pintype "passive"))
      (node (ref "C219") (pin "1") (pinfunction "+_1") (pintype "passive"))
      (node (ref "C220") (pin "1") (pinfunction "+_1") (pintype "passive"))
      (node (ref "C221") (pin "1") (pinfunction "+_1") (pintype "passive"))
      (node (ref "C222") (pin "1") (pinfunction "+_1") (pintype "passive"))
      (node (ref "C223") (pin "1") (pinfunction "+_1") (pintype "passive"))
      (node (ref "C224") (pin "1") (pinfunction "+_1") (pintype "passive"))
      (node (ref "C225") (pin "1") (pinfunction "+_1") (pintype "passive"))
      (node (ref "C226") (pin "1") (pinfunction "+_1") (pintype "passive"))
      (node (ref "C227") (pin "2") (pinfunction "-_2") (pintype "passive"))
      (node (ref "C228") (pin "2") (pinfunction "-_2") (pintype "passive"))
      (node (ref "C229") (pin "1") (pinfunction "+_1") (pintype "passive"))
      (node (ref "C230") (pin "1") (pinfunction "+_1") (pintype "passive"))
      (node (ref "C231") (pin "1") (pinfunction "+_1") (pintype "passive"))
      (node (ref "C232") (pin "1") (pinfunction "+_1") (pintype "passive"))
      (node (ref "C233") (pin "1") (pinfunction "+_1") (pintype "passive"))
      (node (ref "C234") (pin "1") (pinfunction "+_1") (pintype "passive"))
      (node (ref "C235") (pin "1") (pinfunction "+_1") (pintype "passive"))
      (node (ref "C236") (pin "1") (pinfunction "+_1") (pintype "passive"))
      (node (ref "C237") (pin "1") (pinfunction "+_1") (pintype "passive"))
      (node (ref "C238") (pin "1") (pinfunction "+_1") (pintype "passive"))
      (node (ref "C239") (pin "1") (pinfunction "+_1") (pintype "passive"))
      (node (ref "C240") (pin "1") (pinfunction "+_1") (pintype "passive"))
      (node (ref "C241") (pin "1") (pinfunction "+_1") (pintype "passive"))
      (node (ref "C242") (pin "1") (pinfunction "+_1") (pintype "passive"))
      (node (ref "C243") (pin "1") (pinfunction "+_1") (pintype "passive"))
      (node (ref "C244") (pin "1") (pinfunction "+_1") (pintype "passive"))
      (node (ref "C245") (pin "1") (pinfunction "+_1") (pintype "passive"))
      (node (ref "C246") (pin "2") (pinfunction "-_2") (pintype "passive"))
      (node (ref "C247") (pin "2") (pinfunction "-_2") (pintype "passive"))
      (node (ref "C248") (pin "1") (pinfunction "+_1") (pintype "passive"))
      (node (ref "C249") (pin "1") (pinfunction "+_1") (pintype "passive"))
      (node (ref "C250") (pin "1") (pinfunction "+_1") (pintype "passive"))
      (node (ref "C251") (pin "1") (pinfunction "+_1") (pintype "passive"))
      (node (ref "C252") (pin "1") (pinfunction "+_1") (pintype "passive"))
      (node (ref "C253") (pin "1") (pinfunction "+_1") (pintype "passive"))
      (node (ref "C254") (pin "1") (pinfunction "+_1") (pintype "passive"))
      (node (ref "C255") (pin "1") (pinfunction "+_1") (pintype "passive"))
      (node (ref "C256") (pin "1") (pinfunction "+_1") (pintype "passive"))
      (node (ref "C257") (pin "1") (pinfunction "+_1") (pintype "passive"))
      (node (ref "C258") (pin "1") (pinfunction "+_1") (pintype "passive"))
      (node (ref "C259") (pin "1") (pinfunction "+_1") (pintype "passive"))
      (node (ref "C260") (pin "1") (pinfunction "+_1") (pintype "passive"))
      (node (ref "C261") (pin "1") (pinfunction "+_1") (pintype "passive"))
      (node (ref "C262") (pin "1") (pinfunction "+_1") (pintype "passive"))
      (node (ref "C263") (pin "1") (pinfunction "+_1") (pintype "passive"))
      (node (ref "C264") (pin "1") (pinfunction "+_1") (pintype "passive"))
      (node (ref "C265") (pin "1") (pinfunction "+_1") (pintype "passive"))
      (node (ref "C266") (pin "1") (pinfunction "+_1") (pintype "passive"))
      (node (ref "C271") (pin "1") (pinfunction "+_1") (pintype "passive"))
      (node (ref "C272") (pin "1") (pinfunction "+_1") (pintype "passive"))
      (node (ref "C273") (pin "2") (pinfunction "-_2") (pintype "passive"))
      (node (ref "C274") (pin "2") (pinfunction "-_2") (pintype "passive"))
      (node (ref "C275") (pin "2") (pinfunction "-_2") (pintype "passive"))
      (node (ref "C276") (pin "2") (pinfunction "-_2") (pintype "passive"))
      (node (ref "C277") (pin "2") (pinfunction "-_2") (pintype "passive"))
      (node (ref "C278") (pin "2") (pinfunction "-_2") (pintype "passive"))
      (node (ref "C279") (pin "2") (pinfunction "-_2") (pintype "passive"))
      (node (ref "C280") (pin "2") (pinfunction "-_2") (pintype "passive"))
      (node (ref "C281") (pin "2") (pinfunction "-_2") (pintype "passive"))
      (node (ref "C282") (pin "2") (pinfunction "-_2") (pintype "passive"))
      (node (ref "C70") (pin "1") (pinfunction "+_1") (pintype "passive"))
      (node (ref "C87") (pin "2") (pinfunction "-_2") (pintype "passive"))
      (node (ref "C94") (pin "2") (pinfunction "-_2") (pintype "passive"))
      (node (ref "D2") (pin "A12") (pinfunction "GND_A12") (pintype "power_in"))
      (node (ref "D2") (pin "A17") (pinfunction "GND_A17") (pintype "power_in"))
      (node (ref "D2") (pin "A2") (pinfunction "GND_A2") (pintype "power_in"))
      (node (ref "D2") (pin "A22") (pinfunction "GND_A22") (pintype "power_in"))
      (node (ref "D2") (pin "A26") (pinfunction "GND_A26") (pintype "power_in"))
      (node (ref "D2") (pin "A27") (pinfunction "GND_A27") (pintype "power_in"))
      (node (ref "D2") (pin "AA11") (pinfunction "GND_AA11") (pintype "power_in"))
      (node (ref "D2") (pin "AA22") (pinfunction "GND_AA22") (pintype "power_in"))
      (node (ref "D2") (pin "AA29") (pinfunction "VREFB5BN0_AA29") (pintype "power_in"))
      (node (ref "D2") (pin "AA3") (pinfunction "GND_AA3") (pintype "power_in"))
      (node (ref "D2") (pin "AA4") (pinfunction "GND_AA4") (pintype "power_in"))
      (node (ref "D2") (pin "AA6") (pinfunction "GND_AA6") (pintype "power_in"))
      (node (ref "D2") (pin "AA9") (pinfunction "GND_AA9") (pintype "power_in"))
      (node (ref "D2") (pin "AB1") (pinfunction "GND_AB1") (pintype "power_in"))
      (node (ref "D2") (pin "AB19") (pinfunction "GND_AB19") (pintype "power_in"))
      (node (ref "D2") (pin "AB2") (pinfunction "GND_AB2") (pintype "power_in"))
      (node (ref "D2") (pin "AB29") (pinfunction "GND_AB29") (pintype "power_in"))
      (node (ref "D2") (pin "AB5") (pinfunction "GND_AB5") (pintype "power_in"))
      (node (ref "D2") (pin "AB7") (pinfunction "GND_AB7") (pintype "power_in"))
      (node (ref "D2") (pin "AC16") (pinfunction "GND_AC16") (pintype "power_in"))
      (node (ref "D2") (pin "AC24") (pinfunction "VREFB5AN0_AC24") (pintype "power_in"))
      (node (ref "D2") (pin "AC26") (pinfunction "GND_AC26") (pintype "power_in"))
      (node (ref "D2") (pin "AC3") (pinfunction "GND_AC3") (pintype "power_in"))
      (node (ref "D2") (pin "AC4") (pinfunction "GND_AC4") (pintype "power_in"))
      (node (ref "D2") (pin "AC6") (pinfunction "GND_AC6") (pintype "power_in"))
      (node (ref "D2") (pin "AC8") (pinfunction "GND_AC8") (pintype "power_in"))
      (node (ref "D2") (pin "AD1") (pinfunction "GND_AD1") (pintype "power_in"))
      (node (ref "D2") (pin "AD2") (pinfunction "GND_AD2") (pintype "power_in"))
      (node (ref "D2") (pin "AD23") (pinfunction "GND_AD23") (pintype "power_in"))
      (node (ref "D2") (pin "AD5") (pinfunction "GND_AD5") (pintype "power_in"))
      (node (ref "D2") (pin "AD6") (pinfunction "VREFB3AN0_AD6") (pintype "power_in"))
      (node (ref "D2") (pin "AE10") (pinfunction "GND_AE10") (pintype "power_in"))
      (node (ref "D2") (pin "AE20") (pinfunction "GND_AE20") (pintype "power_in"))
      (node (ref "D2") (pin "AE3") (pinfunction "GND_AE3") (pintype "power_in"))
      (node (ref "D2") (pin "AE4") (pinfunction "GND_AE4") (pintype "power_in"))
      (node (ref "D2") (pin "AF1") (pinfunction "GND_AF1") (pintype "power_in"))
      (node (ref "D2") (pin "AF12") (pinfunction "GND_AF12") (pintype "power_in"))
      (node (ref "D2") (pin "AF17") (pinfunction "GND_AF17") (pintype "power_in"))
      (node (ref "D2") (pin "AF2") (pinfunction "GND_AF2") (pintype "power_in"))
      (node (ref "D2") (pin "AF27") (pinfunction "GND_AF27") (pintype "power_in"))
      (node (ref "D2") (pin "AF3") (pinfunction "GND_AF3") (pintype "power_in"))
      (node (ref "D2") (pin "AG14") (pinfunction "GND_AG14") (pintype "power_in"))
      (node (ref "D2") (pin "AG24") (pinfunction "GND_AG24") (pintype "power_in"))
      (node (ref "D2") (pin "AG9") (pinfunction "GND_AG9") (pintype "power_in"))
      (node (ref "D2") (pin "AH1") (pinfunction "GND_AH1") (pintype "power_in"))
      (node (ref "D2") (pin "AH11") (pinfunction "GND_AH11") (pintype "power_in"))
      (node (ref "D2") (pin "AH21") (pinfunction "GND_AH21") (pintype "power_in"))
      (node (ref "D2") (pin "AH6") (pinfunction "GND_AH6") (pintype "power_in"))
      (node (ref "D2") (pin "AJ18") (pinfunction "GND_AJ18") (pintype "power_in"))
      (node (ref "D2") (pin "AJ28") (pinfunction "GND_AJ28") (pintype "power_in"))
      (node (ref "D2") (pin "AJ3") (pinfunction "GND_AJ3") (pintype "power_in"))
      (node (ref "D2") (pin "AJ30") (pinfunction "GND_AJ30") (pintype "power_in"))
      (node (ref "D2") (pin "AK15") (pinfunction "GND_AK15") (pintype "power_in"))
      (node (ref "D2") (pin "AK25") (pinfunction "GND_AK25") (pintype "power_in"))
      (node (ref "D2") (pin "AK5") (pinfunction "GND_AK5") (pintype "power_in"))
      (node (ref "D2") (pin "B10") (pinfunction "VREFB8AN0_B10") (pintype "power_in"))
      (node (ref "D2") (pin "B14") (pinfunction "GND_B14") (pintype "power_in"))
      (node (ref "D2") (pin "B19") (pinfunction "GND_B19") (pintype "power_in"))
      (node (ref "D2") (pin "B24") (pinfunction "GND_B24") (pintype "power_in"))
      (node (ref "D2") (pin "B29") (pinfunction "GND_B29") (pintype "power_in"))
      (node (ref "D2") (pin "B9") (pinfunction "GND_B9") (pintype "power_in"))
      (node (ref "D2") (pin "C1") (pinfunction "GND_C1") (pintype "power_in"))
      (node (ref "D2") (pin "C16") (pinfunction "GND_C16") (pintype "power_in"))
      (node (ref "D2") (pin "C21") (pinfunction "GND_C21") (pintype "power_in"))
      (node (ref "D2") (pin "C26") (pinfunction "GND_C26") (pintype "power_in"))
      (node (ref "D2") (pin "C6") (pinfunction "GND_C6") (pintype "power_in"))
      (node (ref "D2") (pin "D13") (pinfunction "GND_D13") (pintype "power_in"))
      (node (ref "D2") (pin "D23") (pinfunction "GND_D23") (pintype "power_in"))
      (node (ref "D2") (pin "D26") (pinfunction "GND_D26") (pintype "power_in"))
      (node (ref "D2") (pin "D3") (pinfunction "GND_D3") (pintype "power_in"))
      (node (ref "D2") (pin "E10") (pinfunction "GND_E10") (pintype "power_in"))
      (node (ref "D2") (pin "E22") (pinfunction "VREFB7A7B7C7DN0_HPS_E22") (pintype "power_in"))
      (node (ref "D2") (pin "E25") (pinfunction "GND_E25") (pintype "power_in"))
      (node (ref "D2") (pin "E30") (pinfunction "GND_E30") (pintype "power_in"))
      (node (ref "D2") (pin "F17") (pinfunction "GND_F17") (pintype "power_in"))
      (node (ref "D2") (pin "F2") (pinfunction "GND_F2") (pintype "power_in"))
      (node (ref "D2") (pin "F27") (pinfunction "GND_F27") (pintype "power_in"))
      (node (ref "D2") (pin "F5") (pinfunction "GND_F5") (pintype "power_in"))
      (node (ref "D2") (pin "F7") (pinfunction "GND_F7") (pintype "power_in"))
      (node (ref "D2") (pin "G24") (pinfunction "GND_G24") (pintype "power_in"))
      (node (ref "D2") (pin "G3") (pinfunction "GND_G3") (pintype "power_in"))
      (node (ref "D2") (pin "G4") (pinfunction "GND_G4") (pintype "power_in"))
      (node (ref "D2") (pin "H1") (pinfunction "GND_H1") (pintype "power_in"))
      (node (ref "D2") (pin "H11") (pinfunction "GND_H11") (pintype "power_in"))
      (node (ref "D2") (pin "H2") (pinfunction "GND_H2") (pintype "power_in"))
      (node (ref "D2") (pin "H5") (pinfunction "GND_H5") (pintype "power_in"))
      (node (ref "D2") (pin "J18") (pinfunction "GND_J18") (pintype "power_in"))
      (node (ref "D2") (pin "J22") (pinfunction "GND_J22") (pintype "power_in"))
      (node (ref "D2") (pin "J28") (pinfunction "GND_J28") (pintype "power_in"))
      (node (ref "D2") (pin "J3") (pinfunction "GND_J3") (pintype "power_in"))
      (node (ref "D2") (pin "J4") (pinfunction "GND_J4") (pintype "power_in"))
      (node (ref "D2") (pin "J6") (pinfunction "GND_J6") (pintype "power_in"))
      (node (ref "D2") (pin "J8") (pinfunction "GND_J8") (pintype "power_in"))
      (node (ref "D2") (pin "K1") (pinfunction "GND_K1") (pintype "power_in"))
      (node (ref "D2") (pin "K10") (pinfunction "GND_K10") (pintype "power_in"))
      (node (ref "D2") (pin "K15") (pinfunction "GND_K15") (pintype "power_in"))
      (node (ref "D2") (pin "K2") (pinfunction "GND_K2") (pintype "power_in"))
      (node (ref "D2") (pin "K20") (pinfunction "GND_K20") (pintype "power_in"))
      (node (ref "D2") (pin "K25") (pinfunction "GND_K25") (pintype "power_in"))
      (node (ref "D2") (pin "K5") (pinfunction "GND_K5") (pintype "power_in"))
      (node (ref "D2") (pin "L11") (pinfunction "GND_L11") (pintype "power_in"))
      (node (ref "D2") (pin "L13") (pinfunction "GND_L13") (pintype "power_in"))
      (node (ref "D2") (pin "L15") (pinfunction "GND_L15") (pintype "power_in"))
      (node (ref "D2") (pin "L17") (pinfunction "GND_L17") (pintype "power_in"))
      (node (ref "D2") (pin "L19") (pinfunction "GND_L19") (pintype "power_in"))
      (node (ref "D2") (pin "L22") (pinfunction "GND_L22") (pintype "power_in"))
      (node (ref "D2") (pin "L3") (pinfunction "GND_L3") (pintype "power_in"))
      (node (ref "D2") (pin "L4") (pinfunction "GND_L4") (pintype "power_in"))
      (node (ref "D2") (pin "L6") (pinfunction "GND_L6") (pintype "power_in"))
      (node (ref "D2") (pin "M1") (pinfunction "GND_M1") (pintype "power_in"))
      (node (ref "D2") (pin "M10") (pinfunction "GND_M10") (pintype "power_in"))
      (node (ref "D2") (pin "M12") (pinfunction "GND_M12") (pintype "power_in"))
      (node (ref "D2") (pin "M14") (pinfunction "GND_M14") (pintype "power_in"))
      (node (ref "D2") (pin "M16") (pinfunction "GND_M16") (pintype "power_in"))
      (node (ref "D2") (pin "M18") (pinfunction "GND_M18") (pintype "power_in"))
      (node (ref "D2") (pin "M2") (pinfunction "GND_M2") (pintype "power_in"))
      (node (ref "D2") (pin "M20") (pinfunction "GND_M20") (pintype "power_in"))
      (node (ref "D2") (pin "M29") (pinfunction "GND_M29") (pintype "power_in"))
      (node (ref "D2") (pin "M5") (pinfunction "GND_M5") (pintype "power_in"))
      (node (ref "D2") (pin "M7") (pinfunction "GND_M7") (pintype "power_in"))
      (node (ref "D2") (pin "M8") (pinfunction "GND_M8") (pintype "power_in"))
      (node (ref "D2") (pin "N11") (pinfunction "GND_N11") (pintype "power_in"))
      (node (ref "D2") (pin "N13") (pinfunction "GND_N13") (pintype "power_in"))
      (node (ref "D2") (pin "N15") (pinfunction "GND_N15") (pintype "power_in"))
      (node (ref "D2") (pin "N17") (pinfunction "GND_N17") (pintype "power_in"))
      (node (ref "D2") (pin "N19") (pinfunction "GND_N19") (pintype "power_in"))
      (node (ref "D2") (pin "N26") (pinfunction "GND_N26") (pintype "power_in"))
      (node (ref "D2") (pin "N3") (pinfunction "GND_N3") (pintype "power_in"))
      (node (ref "D2") (pin "N4") (pinfunction "GND_N4") (pintype "power_in"))
      (node (ref "D2") (pin "N6") (pinfunction "GND_N6") (pintype "power_in"))
      (node (ref "D2") (pin "N8") (pinfunction "GND_N8") (pintype "power_in"))
      (node (ref "D2") (pin "N9") (pinfunction "GND_N9") (pintype "power_in"))
      (node (ref "D2") (pin "P1") (pinfunction "GND_P1") (pintype "power_in"))
      (node (ref "D2") (pin "P10") (pinfunction "GND_P10") (pintype "power_in"))
      (node (ref "D2") (pin "P12") (pinfunction "GND_P12") (pintype "power_in"))
      (node (ref "D2") (pin "P14") (pinfunction "GND_P14") (pintype "power_in"))
      (node (ref "D2") (pin "P16") (pinfunction "GND_P16") (pintype "power_in"))
      (node (ref "D2") (pin "P18") (pinfunction "GND_P18") (pintype "power_in"))
      (node (ref "D2") (pin "P2") (pinfunction "GND_P2") (pintype "power_in"))
      (node (ref "D2") (pin "P20") (pinfunction "GND_P20") (pintype "power_in"))
      (node (ref "D2") (pin "P5") (pinfunction "GND_P5") (pintype "power_in"))
      (node (ref "D2") (pin "P7") (pinfunction "GND_P7") (pintype "power_in"))
      (node (ref "D2") (pin "R11") (pinfunction "GND_R11") (pintype "power_in"))
      (node (ref "D2") (pin "R13") (pinfunction "GND_R13") (pintype "power_in"))
      (node (ref "D2") (pin "R15") (pinfunction "GND_R15") (pintype "power_in"))
      (node (ref "D2") (pin "R17") (pinfunction "GND_R17") (pintype "power_in"))
      (node (ref "D2") (pin "R3") (pinfunction "GND_R3") (pintype "power_in"))
      (node (ref "D2") (pin "R30") (pinfunction "GND_R30") (pintype "power_in"))
      (node (ref "D2") (pin "R4") (pinfunction "GND_R4") (pintype "power_in"))
      (node (ref "D2") (pin "R6") (pinfunction "GND_R6") (pintype "power_in"))
      (node (ref "D2") (pin "R8") (pinfunction "GND_R8") (pintype "power_in"))
      (node (ref "D2") (pin "R9") (pinfunction "GND_R9") (pintype "power_in"))
      (node (ref "D2") (pin "T1") (pinfunction "GND_T1") (pintype "power_in"))
      (node (ref "D2") (pin "T10") (pinfunction "GND_T10") (pintype "power_in"))
      (node (ref "D2") (pin "T12") (pinfunction "GND_T12") (pintype "power_in"))
      (node (ref "D2") (pin "T14") (pinfunction "GND_T14") (pintype "power_in"))
      (node (ref "D2") (pin "T15") (pinfunction "GND_T15") (pintype "power_in"))
      (node (ref "D2") (pin "T16") (pinfunction "GND_T16") (pintype "power_in"))
      (node (ref "D2") (pin "T18") (pinfunction "GND_T18") (pintype "power_in"))
      (node (ref "D2") (pin "T2") (pinfunction "GND_T2") (pintype "power_in"))
      (node (ref "D2") (pin "T20") (pinfunction "GND_T20") (pintype "power_in"))
      (node (ref "D2") (pin "T27") (pinfunction "GND_T27") (pintype "power_in"))
      (node (ref "D2") (pin "T5") (pinfunction "GND_T5") (pintype "power_in"))
      (node (ref "D2") (pin "T7") (pinfunction "GND_T7") (pintype "power_in"))
      (node (ref "D2") (pin "U11") (pinfunction "GND_U11") (pintype "power_in"))
      (node (ref "D2") (pin "U13") (pinfunction "GND_U13") (pintype "power_in"))
      (node (ref "D2") (pin "U15") (pinfunction "GND_U15") (pintype "power_in"))
      (node (ref "D2") (pin "U17") (pinfunction "GND_U17") (pintype "power_in"))
      (node (ref "D2") (pin "U22") (pinfunction "GND_U22") (pintype "power_in"))
      (node (ref "D2") (pin "U24") (pinfunction "GND_U24") (pintype "power_in"))
      (node (ref "D2") (pin "U29") (pinfunction "GND_U29") (pintype "power_in"))
      (node (ref "D2") (pin "U3") (pinfunction "GND_U3") (pintype "power_in"))
      (node (ref "D2") (pin "U4") (pinfunction "GND_U4") (pintype "power_in"))
      (node (ref "D2") (pin "U6") (pinfunction "GND_U6") (pintype "power_in"))
      (node (ref "D2") (pin "U9") (pinfunction "GND_U9") (pintype "power_in"))
      (node (ref "D2") (pin "V1") (pinfunction "GND_V1") (pintype "power_in"))
      (node (ref "D2") (pin "V10") (pinfunction "GND_V10") (pintype "power_in"))
      (node (ref "D2") (pin "V12") (pinfunction "GND_V12") (pintype "power_in"))
      (node (ref "D2") (pin "V14") (pinfunction "GND_V14") (pintype "power_in"))
      (node (ref "D2") (pin "V19") (pinfunction "GND_V19") (pintype "power_in"))
      (node (ref "D2") (pin "V2") (pinfunction "GND_V2") (pintype "power_in"))
      (node (ref "D2") (pin "V21") (pinfunction "GND_V21") (pintype "power_in"))
      (node (ref "D2") (pin "V5") (pinfunction "GND_V5") (pintype "power_in"))
      (node (ref "D2") (pin "V7") (pinfunction "GND_V7") (pintype "power_in"))
      (node (ref "D2") (pin "W11") (pinfunction "GND_W11") (pintype "power_in"))
      (node (ref "D2") (pin "W13") (pinfunction "GND_W13") (pintype "power_in"))
      (node (ref "D2") (pin "W18") (pinfunction "GND_W18") (pintype "power_in"))
      (node (ref "D2") (pin "W28") (pinfunction "GND_W28") (pintype "power_in"))
      (node (ref "D2") (pin "W3") (pinfunction "GND_W3") (pintype "power_in"))
      (node (ref "D2") (pin "W4") (pinfunction "GND_W4") (pintype "power_in"))
      (node (ref "D2") (pin "W6") (pinfunction "GND_W6") (pintype "power_in"))
      (node (ref "D2") (pin "W9") (pinfunction "GND_W9") (pintype "power_in"))
      (node (ref "D2") (pin "Y1") (pinfunction "GND_Y1") (pintype "power_in"))
      (node (ref "D2") (pin "Y10") (pinfunction "GND_Y10") (pintype "power_in"))
      (node (ref "D2") (pin "Y12") (pinfunction "GND_Y12") (pintype "power_in"))
      (node (ref "D2") (pin "Y14") (pinfunction "GND_Y14") (pintype "power_in"))
      (node (ref "D2") (pin "Y15") (pinfunction "GND_Y15") (pintype "power_in"))
      (node (ref "D2") (pin "Y2") (pinfunction "GND_Y2") (pintype "power_in"))
      (node (ref "D2") (pin "Y20") (pinfunction "GND_Y20") (pintype "power_in"))
      (node (ref "D2") (pin "Y25") (pinfunction "GND_Y25") (pintype "power_in"))
      (node (ref "D2") (pin "Y30") (pinfunction "GND_Y30") (pintype "power_in"))
      (node (ref "D2") (pin "Y5") (pinfunction "GND_Y5") (pintype "power_in"))
      (node (ref "D2") (pin "Y7") (pinfunction "GND_Y7") (pintype "power_in"))
      (node (ref "D2") (pin "Y8") (pinfunction "GND_Y8") (pintype "power_in"))
    )
    (net (code "4") (name "VCC1P1") (class "Default")
      (node (ref "C113") (pin "2") (pinfunction "-_2") (pintype "passive"))
      (node (ref "C114") (pin "2") (pinfunction "-_2") (pintype "passive"))
      (node (ref "C115") (pin "2") (pinfunction "-_2") (pintype "passive"))
      (node (ref "C116") (pin "2") (pinfunction "-_2") (pintype "passive"))
      (node (ref "C117") (pin "2") (pinfunction "-_2") (pintype "passive"))
      (node (ref "C118") (pin "2") (pinfunction "-_2") (pintype "passive"))
      (node (ref "C119") (pin "2") (pinfunction "-_2") (pintype "passive"))
      (node (ref "C120") (pin "2") (pinfunction "-_2") (pintype "passive"))
      (node (ref "C127") (pin "2") (pinfunction "-_2") (pintype "passive"))
      (node (ref "C128") (pin "2") (pinfunction "-_2") (pintype "passive"))
      (node (ref "C129") (pin "2") (pinfunction "-_2") (pintype "passive"))
      (node (ref "C130") (pin "2") (pinfunction "-_2") (pintype "passive"))
      (node (ref "C131") (pin "2") (pinfunction "-_2") (pintype "passive"))
      (node (ref "C132") (pin "2") (pinfunction "-_2") (pintype "passive"))
      (node (ref "C133") (pin "2") (pinfunction "-_2") (pintype "passive"))
      (node (ref "C134") (pin "2") (pinfunction "-_2") (pintype "passive"))
      (node (ref "C146") (pin "2") (pinfunction "-_2") (pintype "passive"))
      (node (ref "C147") (pin "2") (pinfunction "-_2") (pintype "passive"))
      (node (ref "C148") (pin "2") (pinfunction "-_2") (pintype "passive"))
      (node (ref "C149") (pin "2") (pinfunction "-_2") (pintype "passive"))
      (node (ref "C150") (pin "2") (pinfunction "-_2") (pintype "passive"))
      (node (ref "C151") (pin "2") (pinfunction "-_2") (pintype "passive"))
      (node (ref "C152") (pin "2") (pinfunction "-_2") (pintype "passive"))
      (node (ref "C153") (pin "2") (pinfunction "-_2") (pintype "passive"))
      (node (ref "C168") (pin "1") (pinfunction "+_1") (pintype "passive"))
      (node (ref "C169") (pin "1") (pinfunction "+_1") (pintype "passive"))
      (node (ref "C170") (pin "1") (pinfunction "+_1") (pintype "passive"))
      (node (ref "C171") (pin "1") (pinfunction "+_1") (pintype "passive"))
      (node (ref "C172") (pin "1") (pinfunction "+_1") (pintype "passive"))
      (node (ref "C173") (pin "1") (pinfunction "+_1") (pintype "passive"))
      (node (ref "C174") (pin "1") (pinfunction "+_1") (pintype "passive"))
      (node (ref "C180") (pin "1") (pinfunction "+_1") (pintype "passive"))
      (node (ref "C181") (pin "1") (pinfunction "+_1") (pintype "passive"))
      (node (ref "C182") (pin "1") (pinfunction "+_1") (pintype "passive"))
      (node (ref "C183") (pin "1") (pinfunction "+_1") (pintype "passive"))
      (node (ref "C184") (pin "1") (pinfunction "+_1") (pintype "passive"))
      (node (ref "C185") (pin "1") (pinfunction "+_1") (pintype "passive"))
      (node (ref "C186") (pin "1") (pinfunction "+_1") (pintype "passive"))
      (node (ref "C187") (pin "1") (pinfunction "+_1") (pintype "passive"))
      (node (ref "C189") (pin "1") (pinfunction "+_1") (pintype "passive"))
      (node (ref "C190") (pin "1") (pinfunction "+_1") (pintype "passive"))
      (node (ref "C191") (pin "1") (pinfunction "+_1") (pintype "passive"))
      (node (ref "C192") (pin "1") (pinfunction "+_1") (pintype "passive"))
      (node (ref "C193") (pin "1") (pinfunction "+_1") (pintype "passive"))
      (node (ref "C199") (pin "2") (pinfunction "-_2") (pintype "passive"))
      (node (ref "C200") (pin "2") (pinfunction "-_2") (pintype "passive"))
      (node (ref "C201") (pin "2") (pinfunction "-_2") (pintype "passive"))
      (node (ref "C202") (pin "1") (pinfunction "+_1") (pintype "passive"))
      (node (ref "C203") (pin "1") (pinfunction "+_1") (pintype "passive"))
      (node (ref "C204") (pin "1") (pinfunction "+_1") (pintype "passive"))
      (node (ref "C205") (pin "1") (pinfunction "+_1") (pintype "passive"))
      (node (ref "C210") (pin "2") (pinfunction "-_2") (pintype "passive"))
      (node (ref "C211") (pin "2") (pinfunction "-_2") (pintype "passive"))
      (node (ref "C212") (pin "2") (pinfunction "-_2") (pintype "passive"))
      (node (ref "C213") (pin "2") (pinfunction "-_2") (pintype "passive"))
      (node (ref "C214") (pin "2") (pinfunction "-_2") (pintype "passive"))
      (node (ref "C215") (pin "2") (pinfunction "-_2") (pintype "passive"))
      (node (ref "C216") (pin "2") (pinfunction "-_2") (pintype "passive"))
      (node (ref "C94") (pin "1") (pinfunction "+_1") (pintype "passive"))
      (node (ref "D2") (pin "L16") (pinfunction "VCC_HPS_L16") (pintype "power_in"))
      (node (ref "D2") (pin "L18") (pinfunction "VCC_HPS_L18") (pintype "power_in"))
      (node (ref "D2") (pin "L20") (pinfunction "VCC_HPS_L20") (pintype "power_in"))
      (node (ref "D2") (pin "M11") (pinfunction "VCC_M11") (pintype "power_in"))
      (node (ref "D2") (pin "M13") (pinfunction "VCC_M13") (pintype "power_in"))
      (node (ref "D2") (pin "M15") (pinfunction "VCC_HPS_M15") (pintype "power_in"))
      (node (ref "D2") (pin "M9") (pinfunction "VCC_M9") (pintype "power_in"))
      (node (ref "D2") (pin "N10") (pinfunction "VCC_N10") (pintype "power_in"))
      (node (ref "D2") (pin "N12") (pinfunction "VCC_N12") (pintype "power_in"))
      (node (ref "D2") (pin "N14") (pinfunction "VCC_N14") (pintype "power_in"))
      (node (ref "D2") (pin "N20") (pinfunction "VCC_HPS_N20") (pintype "power_in"))
      (node (ref "D2") (pin "P11") (pinfunction "VCC_P11") (pintype "power_in"))
      (node (ref "D2") (pin "P13") (pinfunction "VCC_P13") (pintype "power_in"))
      (node (ref "D2") (pin "P15") (pinfunction "VCC_HPS_P15") (pintype "power_in"))
      (node (ref "D2") (pin "P17") (pinfunction "VCC_HPS_P17") (pintype "power_in"))
      (node (ref "D2") (pin "P19") (pinfunction "VCC_HPS_P19") (pintype "power_in"))
      (node (ref "D2") (pin "R10") (pinfunction "VCC_R10") (pintype "power_in"))
      (node (ref "D2") (pin "R12") (pinfunction "VCC_R12") (pintype "power_in"))
      (node (ref "D2") (pin "R14") (pinfunction "VCC_R14") (pintype "power_in"))
      (node (ref "D2") (pin "R16") (pinfunction "VCC_HPS_R16") (pintype "power_in"))
      (node (ref "D2") (pin "T11") (pinfunction "VCC_T11") (pintype "power_in"))
      (node (ref "D2") (pin "T13") (pinfunction "VCC_T13") (pintype "power_in"))
      (node (ref "D2") (pin "T17") (pinfunction "VCC_HPS_T17") (pintype "power_in"))
      (node (ref "D2") (pin "T19") (pinfunction "VCC_HPS_T19") (pintype "power_in"))
      (node (ref "D2") (pin "U10") (pinfunction "VCC_U10") (pintype "power_in"))
      (node (ref "D2") (pin "U12") (pinfunction "VCC_U12") (pintype "power_in"))
      (node (ref "D2") (pin "U14") (pinfunction "VCC_U14") (pintype "power_in"))
      (node (ref "D2") (pin "U16") (pinfunction "VCC_HPS_U16") (pintype "power_in"))
      (node (ref "D2") (pin "U18") (pinfunction "VCC_HPS_U18") (pintype "power_in"))
      (node (ref "D2") (pin "U21") (pinfunction "VCC_U21") (pintype "power_in"))
      (node (ref "D2") (pin "V11") (pinfunction "VCC_V11") (pintype "power_in"))
      (node (ref "D2") (pin "V13") (pinfunction "VCC_V13") (pintype "power_in"))
      (node (ref "D2") (pin "V15") (pinfunction "VCC_V15") (pintype "power_in"))
      (node (ref "D2") (pin "W10") (pinfunction "VCC_W10") (pintype "power_in"))
      (node (ref "D2") (pin "W12") (pinfunction "VCC_W12") (pintype "power_in"))
      (node (ref "D2") (pin "W14") (pinfunction "VCC_W14") (pintype "power_in"))
      (node (ref "D2") (pin "Y11") (pinfunction "VCC_Y11") (pintype "power_in"))
      (node (ref "D2") (pin "Y13") (pinfunction "VCC_Y13") (pintype "power_in"))
      (node (ref "D2") (pin "Y9") (pinfunction "VCC_Y9") (pintype "power_in"))
      (node (ref "L2") (pin "2") (pinfunction "2_2") (pintype "passive"))
    )
    (net (code "5") (name "VCC1P5_DDR3") (class "Default")
      (node (ref "C107") (pin "2") (pinfunction "-_2") (pintype "passive"))
      (node (ref "C108") (pin "2") (pinfunction "-_2") (pintype "passive"))
      (node (ref "C109") (pin "2") (pinfunction "-_2") (pintype "passive"))
      (node (ref "C110") (pin "2") (pinfunction "-_2") (pintype "passive"))
      (node (ref "C111") (pin "2") (pinfunction "-_2") (pintype "passive"))
      (node (ref "C175") (pin "1") (pinfunction "+_1") (pintype "passive"))
      (node (ref "C194") (pin "2") (pinfunction "-_2") (pintype "passive"))
      (node (ref "C195") (pin "2") (pinfunction "-_2") (pintype "passive"))
      (node (ref "C196") (pin "2") (pinfunction "-_2") (pintype "passive"))
      (node (ref "C197") (pin "2") (pinfunction "-_2") (pintype "passive"))
      (node (ref "C198") (pin "2") (pinfunction "-_2") (pintype "passive"))
      (node (ref "C220") (pin "2") (pinfunction "-_2") (pintype "passive"))
      (node (ref "C221") (pin "2") (pinfunction "-_2") (pintype "passive"))
      (node (ref "C222") (pin "2") (pinfunction "-_2") (pintype "passive"))
      (node (ref "C223") (pin "2") (pinfunction "-_2") (pintype "passive"))
      (node (ref "C224") (pin "2") (pinfunction "-_2") (pintype "passive"))
      (node (ref "C225") (pin "2") (pinfunction "-_2") (pintype "passive"))
      (node (ref "C227") (pin "1") (pinfunction "+_1") (pintype "passive"))
      (node (ref "C228") (pin "1") (pinfunction "+_1") (pintype "passive"))
      (node (ref "C229") (pin "2") (pinfunction "-_2") (pintype "passive"))
      (node (ref "C230") (pin "2") (pinfunction "-_2") (pintype "passive"))
      (node (ref "C231") (pin "2") (pinfunction "-_2") (pintype "passive"))
      (node (ref "C236") (pin "2") (pinfunction "-_2") (pintype "passive"))
      (node (ref "C237") (pin "2") (pinfunction "-_2") (pintype "passive"))
      (node (ref "C238") (pin "2") (pinfunction "-_2") (pintype "passive"))
      (node (ref "C239") (pin "2") (pinfunction "-_2") (pintype "passive"))
      (node (ref "C240") (pin "2") (pinfunction "-_2") (pintype "passive"))
      (node (ref "C241") (pin "2") (pinfunction "-_2") (pintype "passive"))
      (node (ref "C246") (pin "1") (pinfunction "+_1") (pintype "passive"))
      (node (ref "C247") (pin "1") (pinfunction "+_1") (pintype "passive"))
      (node (ref "C248") (pin "2") (pinfunction "-_2") (pintype "passive"))
      (node (ref "C249") (pin "2") (pinfunction "-_2") (pintype "passive"))
      (node (ref "C250") (pin "2") (pinfunction "-_2") (pintype "passive"))
      (node (ref "C271") (pin "2") (pinfunction "-_2") (pintype "passive"))
      (node (ref "C272") (pin "2") (pinfunction "-_2") (pintype "passive"))
      (node (ref "C273") (pin "1") (pinfunction "+_1") (pintype "passive"))
      (node (ref "C274") (pin "1") (pinfunction "+_1") (pintype "passive"))
      (node (ref "C275") (pin "1") (pinfunction "+_1") (pintype "passive"))
      (node (ref "C276") (pin "1") (pinfunction "+_1") (pintype "passive"))
      (node (ref "C277") (pin "1") (pinfunction "+_1") (pintype "passive"))
      (node (ref "C278") (pin "1") (pinfunction "+_1") (pintype "passive"))
      (node (ref "C279") (pin "1") (pinfunction "+_1") (pintype "passive"))
      (node (ref "C280") (pin "1") (pinfunction "+_1") (pintype "passive"))
      (node (ref "C281") (pin "1") (pinfunction "+_1") (pintype "passive"))
      (node (ref "C282") (pin "1") (pinfunction "+_1") (pintype "passive"))
      (node (ref "D2") (pin "AA17") (pinfunction "VCCIO4A_AA17") (pintype "power_in"))
      (node (ref "D2") (pin "AB14") (pinfunction "VCCIO3B_AB14") (pintype "power_in"))
      (node (ref "D2") (pin "AC21") (pinfunction "VCCIO4A_AC21") (pintype "power_in"))
      (node (ref "D2") (pin "AD13") (pinfunction "VCCIO3B_AD13") (pintype "power_in"))
      (node (ref "D2") (pin "AD18") (pinfunction "VCCIO4A_AD18") (pintype "power_in"))
      (node (ref "D2") (pin "AE15") (pinfunction "VCCIO3B_AE15") (pintype "power_in"))
      (node (ref "D2") (pin "AE25") (pinfunction "VCCIO4A_AE25") (pintype "power_in"))
      (node (ref "D2") (pin "AF22") (pinfunction "VCCIO4A_AF22") (pintype "power_in"))
      (node (ref "D2") (pin "AG19") (pinfunction "VCCIO4A_AG19") (pintype "power_in"))
      (node (ref "D2") (pin "AH16") (pinfunction "VCCIO4A_AH16") (pintype "power_in"))
      (node (ref "D2") (pin "AH26") (pinfunction "VCCIO4A_AH26") (pintype "power_in"))
      (node (ref "D2") (pin "AJ13") (pinfunction "VCCIO3B_AJ13") (pintype "power_in"))
      (node (ref "D2") (pin "AJ23") (pinfunction "VCCIO4A_AJ23") (pintype "power_in"))
      (node (ref "D2") (pin "AJ8") (pinfunction "VCCIO3B_AJ8") (pintype "power_in"))
      (node (ref "D2") (pin "AK10") (pinfunction "VCCIO3B_AK10") (pintype "power_in"))
      (node (ref "D2") (pin "AK20") (pinfunction "VCCIO4A_AK20") (pintype "power_in"))
      (node (ref "D2") (pin "D28") (pinfunction "VCCIO6A_HPS_D28") (pintype "power_in"))
      (node (ref "D2") (pin "G29") (pinfunction "VCCIO6A_HPS_G29") (pintype "power_in"))
      (node (ref "D2") (pin "H26") (pinfunction "VCCIO6A_HPS_H26") (pintype "power_in"))
      (node (ref "D2") (pin "K24") (pinfunction "VCCIO6A_HPS_K24") (pintype "power_in"))
      (node (ref "D2") (pin "K30") (pinfunction "VCCIO6A_HPS_K30") (pintype "power_in"))
      (node (ref "D2") (pin "L27") (pinfunction "VCCIO6A_HPS_L27") (pintype "power_in"))
      (node (ref "D2") (pin "M24") (pinfunction "VCCIO6A_HPS_M24") (pintype "power_in"))
      (node (ref "D2") (pin "N21") (pinfunction "VCCIO6A_HPS_N21") (pintype "power_in"))
      (node (ref "D2") (pin "P23") (pinfunction "VCCIO6B_HPS_P23") (pintype "power_in"))
      (node (ref "D2") (pin "P28") (pinfunction "VCCIO6B_HPS_P28") (pintype "power_in"))
      (node (ref "D2") (pin "R25") (pinfunction "VCCIO6B_HPS_R25") (pintype "power_in"))
      (node (ref "D2") (pin "T22") (pinfunction "VCCIO6B_HPS_T22") (pintype "power_in"))
      (node (ref "D2") (pin "U19") (pinfunction "VCCIO6B_HPS_U19") (pintype "power_in"))
      (node (ref "D2") (pin "V26") (pinfunction "VCCIO6B_HPS_V26") (pintype "power_in"))
    )
    (net (code "6") (name "VCC2P5") (class "Default")
      (node (ref "C112") (pin "1") (pinfunction "+_1") (pintype "passive"))
      (node (ref "C121") (pin "2") (pinfunction "-_2") (pintype "passive"))
      (node (ref "C122") (pin "2") (pinfunction "-_2") (pintype "passive"))
      (node (ref "C135") (pin "2") (pinfunction "-_2") (pintype "passive"))
      (node (ref "C136") (pin "2") (pinfunction "-_2") (pintype "passive"))
      (node (ref "C137") (pin "1") (pinfunction "+_1") (pintype "passive"))
      (node (ref "C142") (pin "2") (pinfunction "-_2") (pintype "passive"))
      (node (ref "C143") (pin "2") (pinfunction "-_2") (pintype "passive"))
      (node (ref "C144") (pin "2") (pinfunction "-_2") (pintype "passive"))
      (node (ref "C145") (pin "2") (pinfunction "-_2") (pintype "passive"))
      (node (ref "C154") (pin "1") (pinfunction "+_1") (pintype "passive"))
      (node (ref "C164") (pin "2") (pinfunction "-_2") (pintype "passive"))
      (node (ref "C165") (pin "2") (pinfunction "-_2") (pintype "passive"))
      (node (ref "C166") (pin "2") (pinfunction "-_2") (pintype "passive"))
      (node (ref "C206") (pin "2") (pinfunction "-_2") (pintype "passive"))
      (node (ref "C207") (pin "2") (pinfunction "-_2") (pintype "passive"))
      (node (ref "C259") (pin "2") (pinfunction "-_2") (pintype "passive"))
      (node (ref "C260") (pin "2") (pinfunction "-_2") (pintype "passive"))
      (node (ref "C261") (pin "2") (pinfunction "-_2") (pintype "passive"))
      (node (ref "C262") (pin "2") (pinfunction "-_2") (pintype "passive"))
      (node (ref "C263") (pin "2") (pinfunction "-_2") (pintype "passive"))
      (node (ref "C264") (pin "2") (pinfunction "-_2") (pintype "passive"))
      (node (ref "C265") (pin "2") (pinfunction "-_2") (pintype "passive"))
      (node (ref "C266") (pin "2") (pinfunction "-_2") (pintype "passive"))
      (node (ref "C87") (pin "1") (pinfunction "+_1") (pintype "passive"))
      (node (ref "D2") (pin "A7") (pinfunction "VCCIO8A_A7") (pintype "power_in"))
      (node (ref "D2") (pin "AA10") (pinfunction "VCCPD3A_AA10") (pintype "power_in"))
      (node (ref "D2") (pin "AA27") (pinfunction "VCCIO5B_AA27") (pintype "power_in"))
      (node (ref "D2") (pin "AB18") (pinfunction "VCCPD3B4A_AB18") (pintype "power_in"))
      (node (ref "D2") (pin "AB20") (pinfunction "VCCPD3B4A_AB20") (pintype "power_in"))
      (node (ref "D2") (pin "AB24") (pinfunction "VCCIO5A_AB24") (pintype "power_in"))
      (node (ref "D2") (pin "AC10") (pinfunction "VCCPD3A_AC10") (pintype "power_in"))
      (node (ref "D2") (pin "AC11") (pinfunction "VCCIO3A_AC11") (pintype "power_in"))
      (node (ref "D2") (pin "AC13") (pinfunction "VCCPD3B4A_AC13") (pintype "power_in"))
      (node (ref "D2") (pin "AC15") (pinfunction "VCCPD3B4A_AC15") (pintype "power_in"))
      (node (ref "D2") (pin "AC17") (pinfunction "VCCPD3B4A_AC17") (pintype "power_in"))
      (node (ref "D2") (pin "AC19") (pinfunction "VCCPD3B4A_AC19") (pintype "power_in"))
      (node (ref "D2") (pin "AD16") (pinfunction "VCCPD3B4A_AD16") (pintype "power_in"))
      (node (ref "D2") (pin "AD28") (pinfunction "VCCIO5A_AD28") (pintype "power_in"))
      (node (ref "D2") (pin "AD8") (pinfunction "VCCIO3A_AD8") (pintype "power_in"))
      (node (ref "D2") (pin "AE21") (pinfunction "VCCPD3B4A_AE21") (pintype "power_in"))
      (node (ref "D2") (pin "AE30") (pinfunction "VCCIO5B_AE30") (pintype "power_in"))
      (node (ref "D2") (pin "AF7") (pinfunction "VCCIO3A_AF7") (pintype "power_in"))
      (node (ref "D2") (pin "AG29") (pinfunction "VCCIO5A_AG29") (pintype "power_in"))
      (node (ref "D2") (pin "AG4") (pinfunction "VCCIO3A_AG4") (pintype "power_in"))
      (node (ref "D2") (pin "B4") (pinfunction "VCCIO8A_B4") (pintype "power_in"))
      (node (ref "D2") (pin "C11") (pinfunction "VCCIO8A_C11") (pintype "power_in"))
      (node (ref "D2") (pin "D8") (pinfunction "VCCIO8A_D8") (pintype "power_in"))
      (node (ref "D2") (pin "E5") (pinfunction "VCCIO8A_E5") (pintype "power_in"))
      (node (ref "D2") (pin "F12") (pinfunction "VCCIO8A_F12") (pintype "power_in"))
      (node (ref "D2") (pin "G14") (pinfunction "VCCIO8A_G14") (pintype "power_in"))
      (node (ref "D2") (pin "G9") (pinfunction "VCCIO8A_G9") (pintype "power_in"))
      (node (ref "D2") (pin "H6") (pinfunction "VCCIO8A_H6") (pintype "power_in"))
      (node (ref "D2") (pin "J13") (pinfunction "VCCIO8A_J13") (pintype "power_in"))
      (node (ref "D2") (pin "K11") (pinfunction "VCCPD8A_K11") (pintype "power_in"))
      (node (ref "D2") (pin "K13") (pinfunction "VCCPD8A_K13") (pintype "power_in"))
      (node (ref "D2") (pin "L10") (pinfunction "VCCPD8A_L10") (pintype "power_in"))
      (node (ref "D2") (pin "L12") (pinfunction "VCCPD8A_L12") (pintype "power_in"))
      (node (ref "D2") (pin "L14") (pinfunction "VCCPD8A_L14") (pintype "power_in"))
      (node (ref "D2") (pin "M21") (pinfunction "VCCPD6A6B_HPS_M21") (pintype "power_in"))
      (node (ref "D2") (pin "N22") (pinfunction "VCCPD6A6B_HPS_N22") (pintype "power_in"))
      (node (ref "D2") (pin "P21") (pinfunction "VCCPD6A6B_HPS_P21") (pintype "power_in"))
      (node (ref "D2") (pin "R20") (pinfunction "VCCPD6A6B_HPS_R20") (pintype "power_in"))
      (node (ref "D2") (pin "R23") (pinfunction "VCCPD6A6B_HPS_R23") (pintype "power_in"))
      (node (ref "D2") (pin "U23") (pinfunction "VCCPD5B_U23") (pintype "power_in"))
      (node (ref "D2") (pin "V22") (pinfunction "VCCPD5A_V22") (pintype "power_in"))
      (node (ref "D2") (pin "V24") (pinfunction "VCCPD5A_V24") (pintype "power_in"))
      (node (ref "D2") (pin "W23") (pinfunction "VCCIO5A_W23") (pintype "power_in"))
      (node (ref "L1") (pin "2") (pinfunction "2_2") (pintype "passive"))
      (node (ref "L13") (pin "2") (pinfunction "2_2") (pintype "passive"))
      (node (ref "L3") (pin "2") (pinfunction "2_2") (pintype "passive"))
      (node (ref "L4") (pin "2") (pinfunction "2_2") (pintype "passive"))
      (node (ref "L5") (pin "1") (pinfunction "1_1") (pintype "passive"))
    )
    (net (code "7") (name "VCC3P3") (class "Default")
      (node (ref "C208") (pin "2") (pinfunction "-_2") (pintype "passive"))
      (node (ref "C209") (pin "2") (pinfunction "-_2") (pintype "passive"))
      (node (ref "C217") (pin "2") (pinfunction "-_2") (pintype "passive"))
      (node (ref "C218") (pin "2") (pinfunction "-_2") (pintype "passive"))
      (node (ref "C219") (pin "2") (pinfunction "-_2") (pintype "passive"))
      (node (ref "C226") (pin "2") (pinfunction "-_2") (pintype "passive"))
      (node (ref "C251") (pin "2") (pinfunction "-_2") (pintype "passive"))
      (node (ref "C252") (pin "2") (pinfunction "-_2") (pintype "passive"))
      (node (ref "C253") (pin "2") (pinfunction "-_2") (pintype "passive"))
      (node (ref "C254") (pin "2") (pinfunction "-_2") (pintype "passive"))
      (node (ref "C255") (pin "2") (pinfunction "-_2") (pintype "passive"))
      (node (ref "C256") (pin "2") (pinfunction "-_2") (pintype "passive"))
      (node (ref "C257") (pin "2") (pinfunction "-_2") (pintype "passive"))
      (node (ref "C258") (pin "2") (pinfunction "-_2") (pintype "passive"))
      (node (ref "D2") (pin "AA23") (pinfunction "VCCPGM_AA23") (pintype "power_in"))
      (node (ref "D2") (pin "AB10") (pinfunction "VCCPGM_AB10") (pintype "power_in"))
      (node (ref "D2") (pin "D18") (pinfunction "VCCIO7C_HPS_D18") (pintype "power_in"))
      (node (ref "D2") (pin "E15") (pinfunction "VCCIO7D_HPS_E15") (pintype "power_in"))
      (node (ref "D2") (pin "E20") (pinfunction "VCCIO7B_HPS_E20") (pintype "power_in"))
      (node (ref "D2") (pin "F22") (pinfunction "VCCIO7A_HPS_F22") (pintype "power_in"))
      (node (ref "D2") (pin "G19") (pinfunction "VCCIO7B_HPS_G19") (pintype "power_in"))
      (node (ref "D2") (pin "H16") (pinfunction "VCCIO7D_HPS_H16") (pintype "power_in"))
      (node (ref "D2") (pin "H21") (pinfunction "VCCIO7A_HPS_H21") (pintype "power_in"))
      (node (ref "D2") (pin "J11") (pinfunction "VCCPGM_J11") (pintype "power_in"))
      (node (ref "D2") (pin "J17") (pinfunction "VCCPD7C_HPS_J17") (pintype "power_in"))
      (node (ref "D2") (pin "K16") (pinfunction "VCCPD7D_HPS_K16") (pintype "power_in"))
      (node (ref "D2") (pin "K18") (pinfunction "VCCPD7B_HPS_K18") (pintype "power_in"))
      (node (ref "D2") (pin "K19") (pinfunction "VCCPD7A_HPS_K19") (pintype "power_in"))
      (node (ref "L6") (pin "1") (pinfunction "1_1") (pintype "passive"))
    )
    (net (code "8") (name "VCCAUX_2p5") (class "Default")
      (node (ref "C138") (pin "2") (pinfunction "-_2") (pintype "passive"))
      (node (ref "C139") (pin "2") (pinfunction "-_2") (pintype "passive"))
      (node (ref "C140") (pin "2") (pinfunction "-_2") (pintype "passive"))
      (node (ref "C141") (pin "2") (pinfunction "-_2") (pintype "passive"))
      (node (ref "D2") (pin "AB11") (pinfunction "VCC_AUX_AB11") (pintype "power_in"))
      (node (ref "D2") (pin "AB16") (pinfunction "VCC_AUX_AB16") (pintype "power_in"))
      (node (ref "D2") (pin "AD22") (pinfunction "VCC_AUX_AD22") (pintype "power_in"))
      (node (ref "D2") (pin "H10") (pinfunction "VCC_AUX_H10") (pintype "power_in"))
      (node (ref "D2") (pin "J16") (pinfunction "VCC_AUX_J16") (pintype "power_in"))
      (node (ref "L3") (pin "1") (pinfunction "1_1") (pintype "passive"))
    )
    (net (code "9") (name "VCCAUX_SH_2p5") (class "Default")
      (node (ref "C176") (pin "2") (pinfunction "-_2") (pintype "passive"))
      (node (ref "C177") (pin "2") (pinfunction "-_2") (pintype "passive"))
      (node (ref "C178") (pin "2") (pinfunction "-_2") (pintype "passive"))
      (node (ref "C179") (pin "2") (pinfunction "-_2") (pintype "passive"))
      (node (ref "D2") (pin "J21") (pinfunction "VCC_AUX_SHARED_J21") (pintype "power_in"))
      (node (ref "L4") (pin "1") (pinfunction "1_1") (pintype "passive"))
    )
    (net (code "10") (name "VCCA_FPLL_2p5") (class "Default")
      (node (ref "C155") (pin "2") (pinfunction "-_2") (pintype "passive"))
      (node (ref "C156") (pin "2") (pinfunction "-_2") (pintype "passive"))
      (node (ref "C157") (pin "2") (pinfunction "-_2") (pintype "passive"))
      (node (ref "C158") (pin "2") (pinfunction "-_2") (pintype "passive"))
      (node (ref "C159") (pin "2") (pinfunction "-_2") (pintype "passive"))
      (node (ref "C160") (pin "2") (pinfunction "-_2") (pintype "passive"))
      (node (ref "C161") (pin "2") (pinfunction "-_2") (pintype "passive"))
      (node (ref "C162") (pin "1") (pinfunction "+_1") (pintype "passive"))
      (node (ref "C163") (pin "1") (pinfunction "+_1") (pintype "passive"))
      (node (ref "D2") (pin "AA8") (pinfunction "VCCA_FPLL_AA8") (pintype "power_in"))
      (node (ref "D2") (pin "K9") (pinfunction "VCCA_FPLL_K9") (pintype "power_in"))
      (node (ref "D2") (pin "N7") (pinfunction "VCCA_FPLL_N7") (pintype "power_in"))
      (node (ref "D2") (pin "R7") (pinfunction "VCCA_FPLL_R7") (pintype "power_in"))
      (node (ref "D2") (pin "V8") (pinfunction "VCCA_FPLL_V8") (pintype "power_in"))
      (node (ref "D2") (pin "Y22") (pinfunction "VCCA_FPLL_Y22") (pintype "power_in"))
      (node (ref "L13") (pin "1") (pinfunction "1_1") (pintype "passive"))
    )
    (net (code "11") (name "VCCH_GXBL_2p5") (class "Default")
      (node (ref "C123") (pin "2") (pinfunction "-_2") (pintype "passive"))
      (node (ref "C124") (pin "2") (pinfunction "-_2") (pintype "passive"))
      (node (ref "C125") (pin "2") (pinfunction "-_2") (pintype "passive"))
      (node (ref "C126") (pin "2") (pinfunction "-_2") (pintype "passive"))
      (node (ref "D2") (pin "AB6") (pinfunction "VCCH_GXBL_AB6") (pintype "power_in"))
      (node (ref "D2") (pin "P6") (pinfunction "VCCH_GXBL_P6") (pintype "power_in"))
      (node (ref "D2") (pin "V6") (pinfunction "VCCH_GXBL_V6") (pintype "power_in"))
      (node (ref "L1") (pin "1") (pinfunction "1_1") (pintype "passive"))
    )
    (net (code "12") (name "VCCL_GXBL_1p1") (class "Default")
      (node (ref "C103") (pin "2") (pinfunction "-_2") (pintype "passive"))
      (node (ref "C105") (pin "2") (pinfunction "-_2") (pintype "passive"))
      (node (ref "C106") (pin "2") (pinfunction "-_2") (pintype "passive"))
      (node (ref "C70") (pin "2") (pinfunction "-_2") (pintype "passive"))
      (node (ref "D2") (pin "AA5") (pinfunction "VCCE_GXBL_AA5") (pintype "power_in"))
      (node (ref "D2") (pin "L5") (pinfunction "VCCL_GXBL_L5") (pintype "power_in"))
      (node (ref "D2") (pin "M6") (pinfunction "VCCE_GXBL_M6") (pintype "power_in"))
      (node (ref "D2") (pin "N5") (pinfunction "VCCE_GXBL_N5") (pintype "power_in"))
      (node (ref "D2") (pin "R5") (pinfunction "VCCL_GXBL_R5") (pintype "power_in"))
      (node (ref "D2") (pin "T6") (pinfunction "VCCE_GXBL_T6") (pintype "power_in"))
      (node (ref "D2") (pin "U5") (pinfunction "VCCE_GXBL_U5") (pintype "power_in"))
      (node (ref "D2") (pin "W5") (pinfunction "VCCL_GXBL_W5") (pintype "power_in"))
      (node (ref "D2") (pin "Y6") (pinfunction "VCCE_GXBL_Y6") (pintype "power_in"))
      (node (ref "L2") (pin "1") (pinfunction "1_1") (pintype "passive"))
    )
    (net (code "13") (name "VCCPLL_HPS_2p5") (class "Default")
      (node (ref "C232") (pin "2") (pinfunction "-_2") (pintype "passive"))
      (node (ref "C233") (pin "2") (pinfunction "-_2") (pintype "passive"))
      (node (ref "C234") (pin "2") (pinfunction "-_2") (pintype "passive"))
      (node (ref "C235") (pin "2") (pinfunction "-_2") (pintype "passive"))
      (node (ref "D2") (pin "L21") (pinfunction "VCCPLL_HPS_L21") (pintype "power_in"))
      (node (ref "L5") (pin "2") (pinfunction "2_2") (pintype "passive"))
    )
    (net (code "14") (name "VCCRSTCLK_HPS") (class "Default")
      (node (ref "C242") (pin "2") (pinfunction "-_2") (pintype "passive"))
      (node (ref "C243") (pin "2") (pinfunction "-_2") (pintype "passive"))
      (node (ref "C244") (pin "2") (pinfunction "-_2") (pintype "passive"))
      (node (ref "C245") (pin "2") (pinfunction "-_2") (pintype "passive"))
      (node (ref "D2") (pin "G23") (pinfunction "VCCRSTCLK_HPS_G23") (pintype "power_in"))
      (node (ref "D2") (pin "J20") (pinfunction "VCCRSTCLK_HPS_J20") (pintype "power_in"))
      (node (ref "L6") (pin "2") (pinfunction "2_2") (pintype "passive"))
    )
    (net (code "15") (name "VCC_BAT") (class "Default")
      (node (ref "C188") (pin "1") (pinfunction "+_1") (pintype "passive"))
      (node (ref "D2") (pin "H9") (pinfunction "VCCBAT_H9") (pintype "power_in"))
    )
  )
)
